# uJOVE5.net
KiCad netlist of a schematic drawn in EAGLE
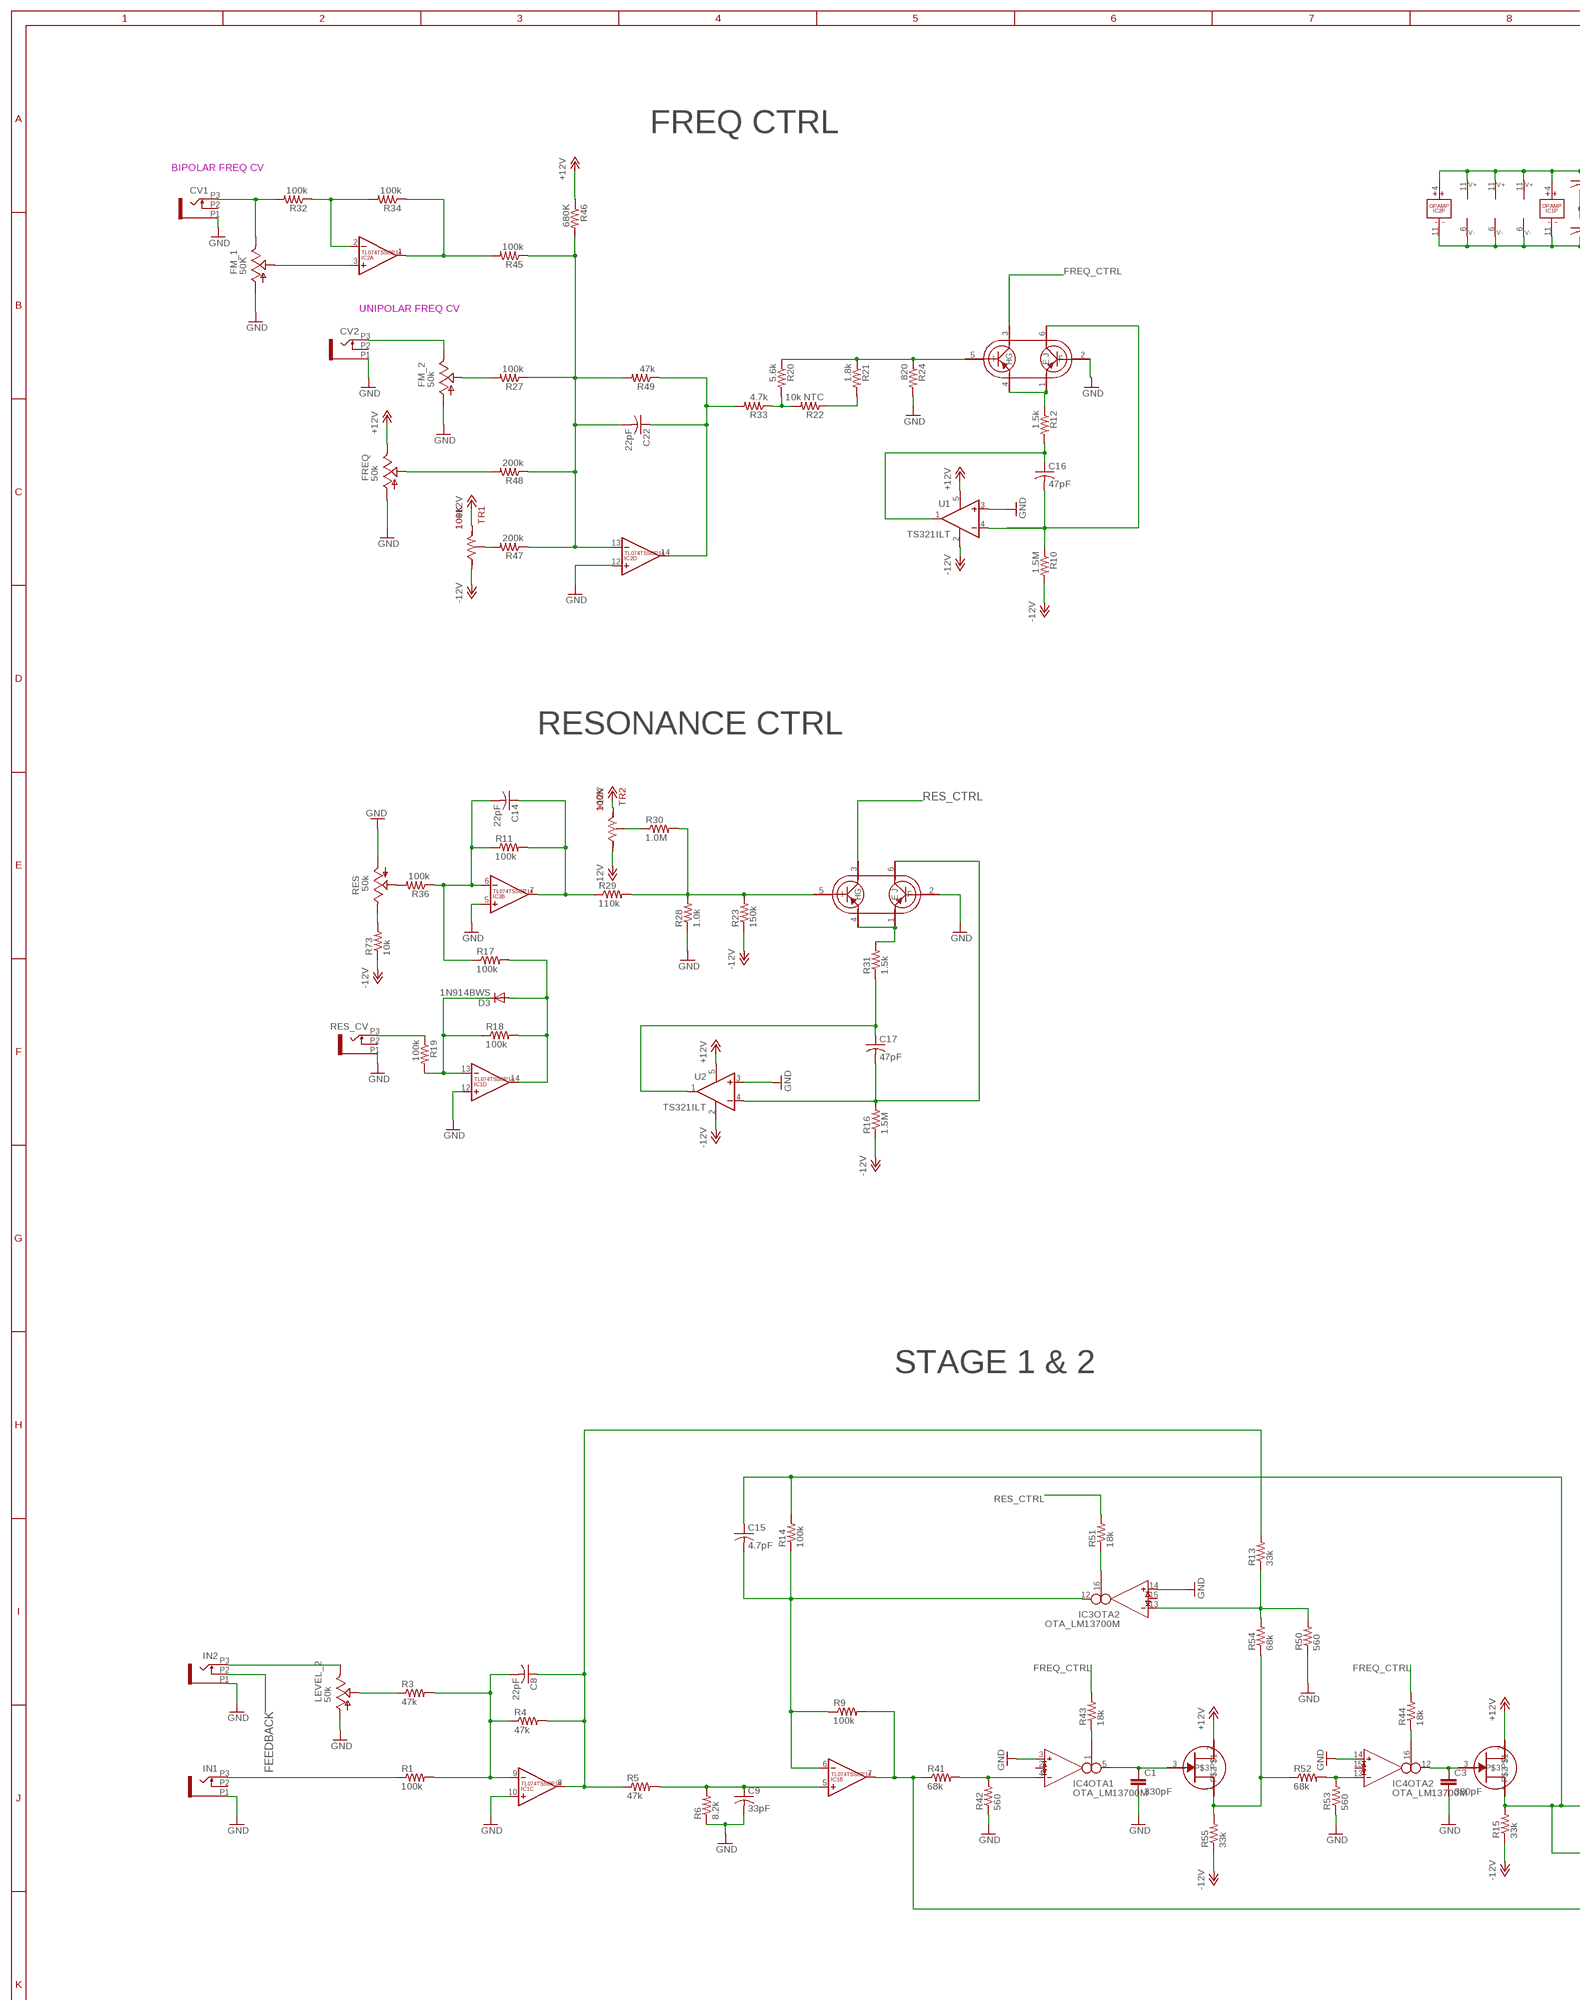
[diagram p0: schematic, sheet 1, part 1 of 3]
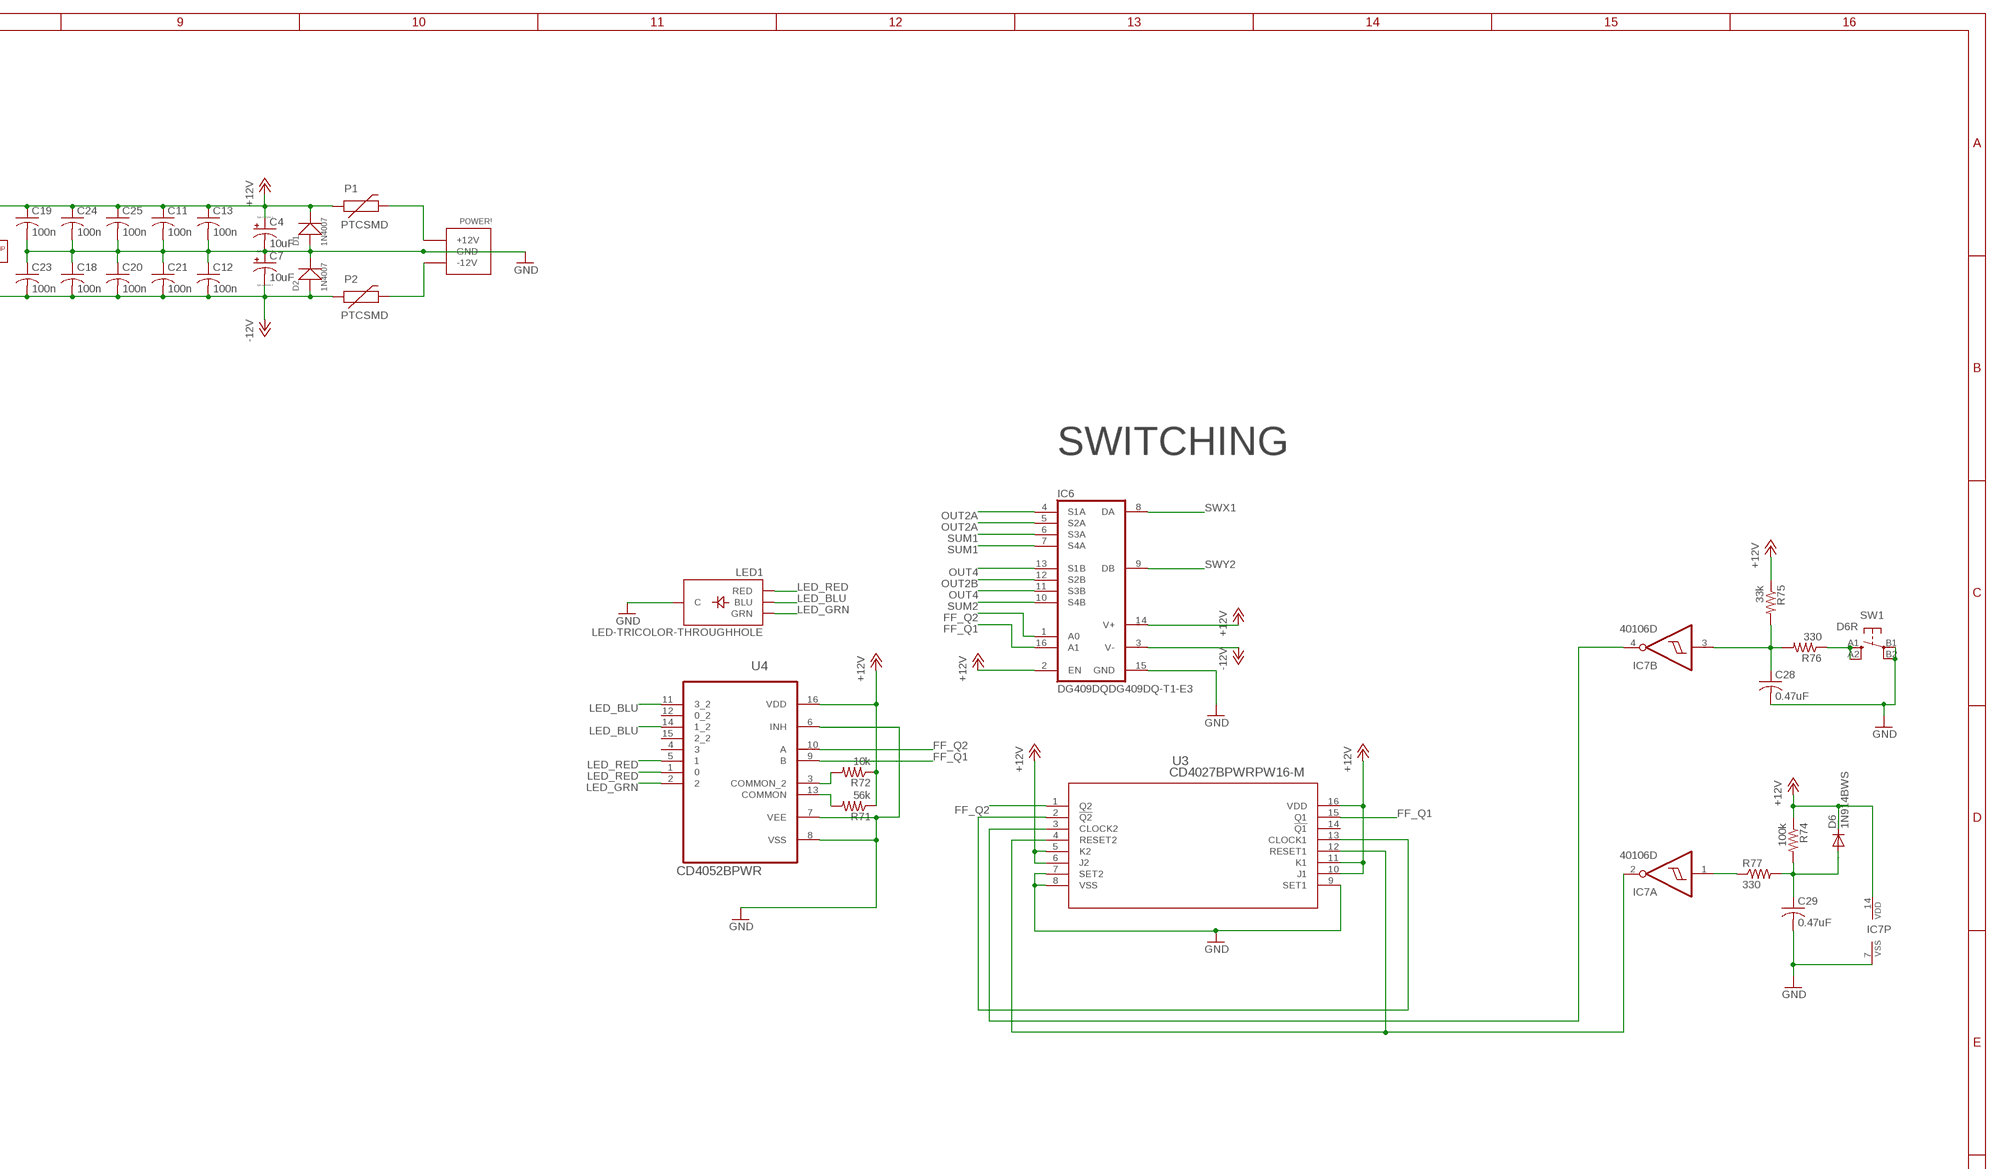
[diagram p1: schematic, sheet 1, part 2 of 3]
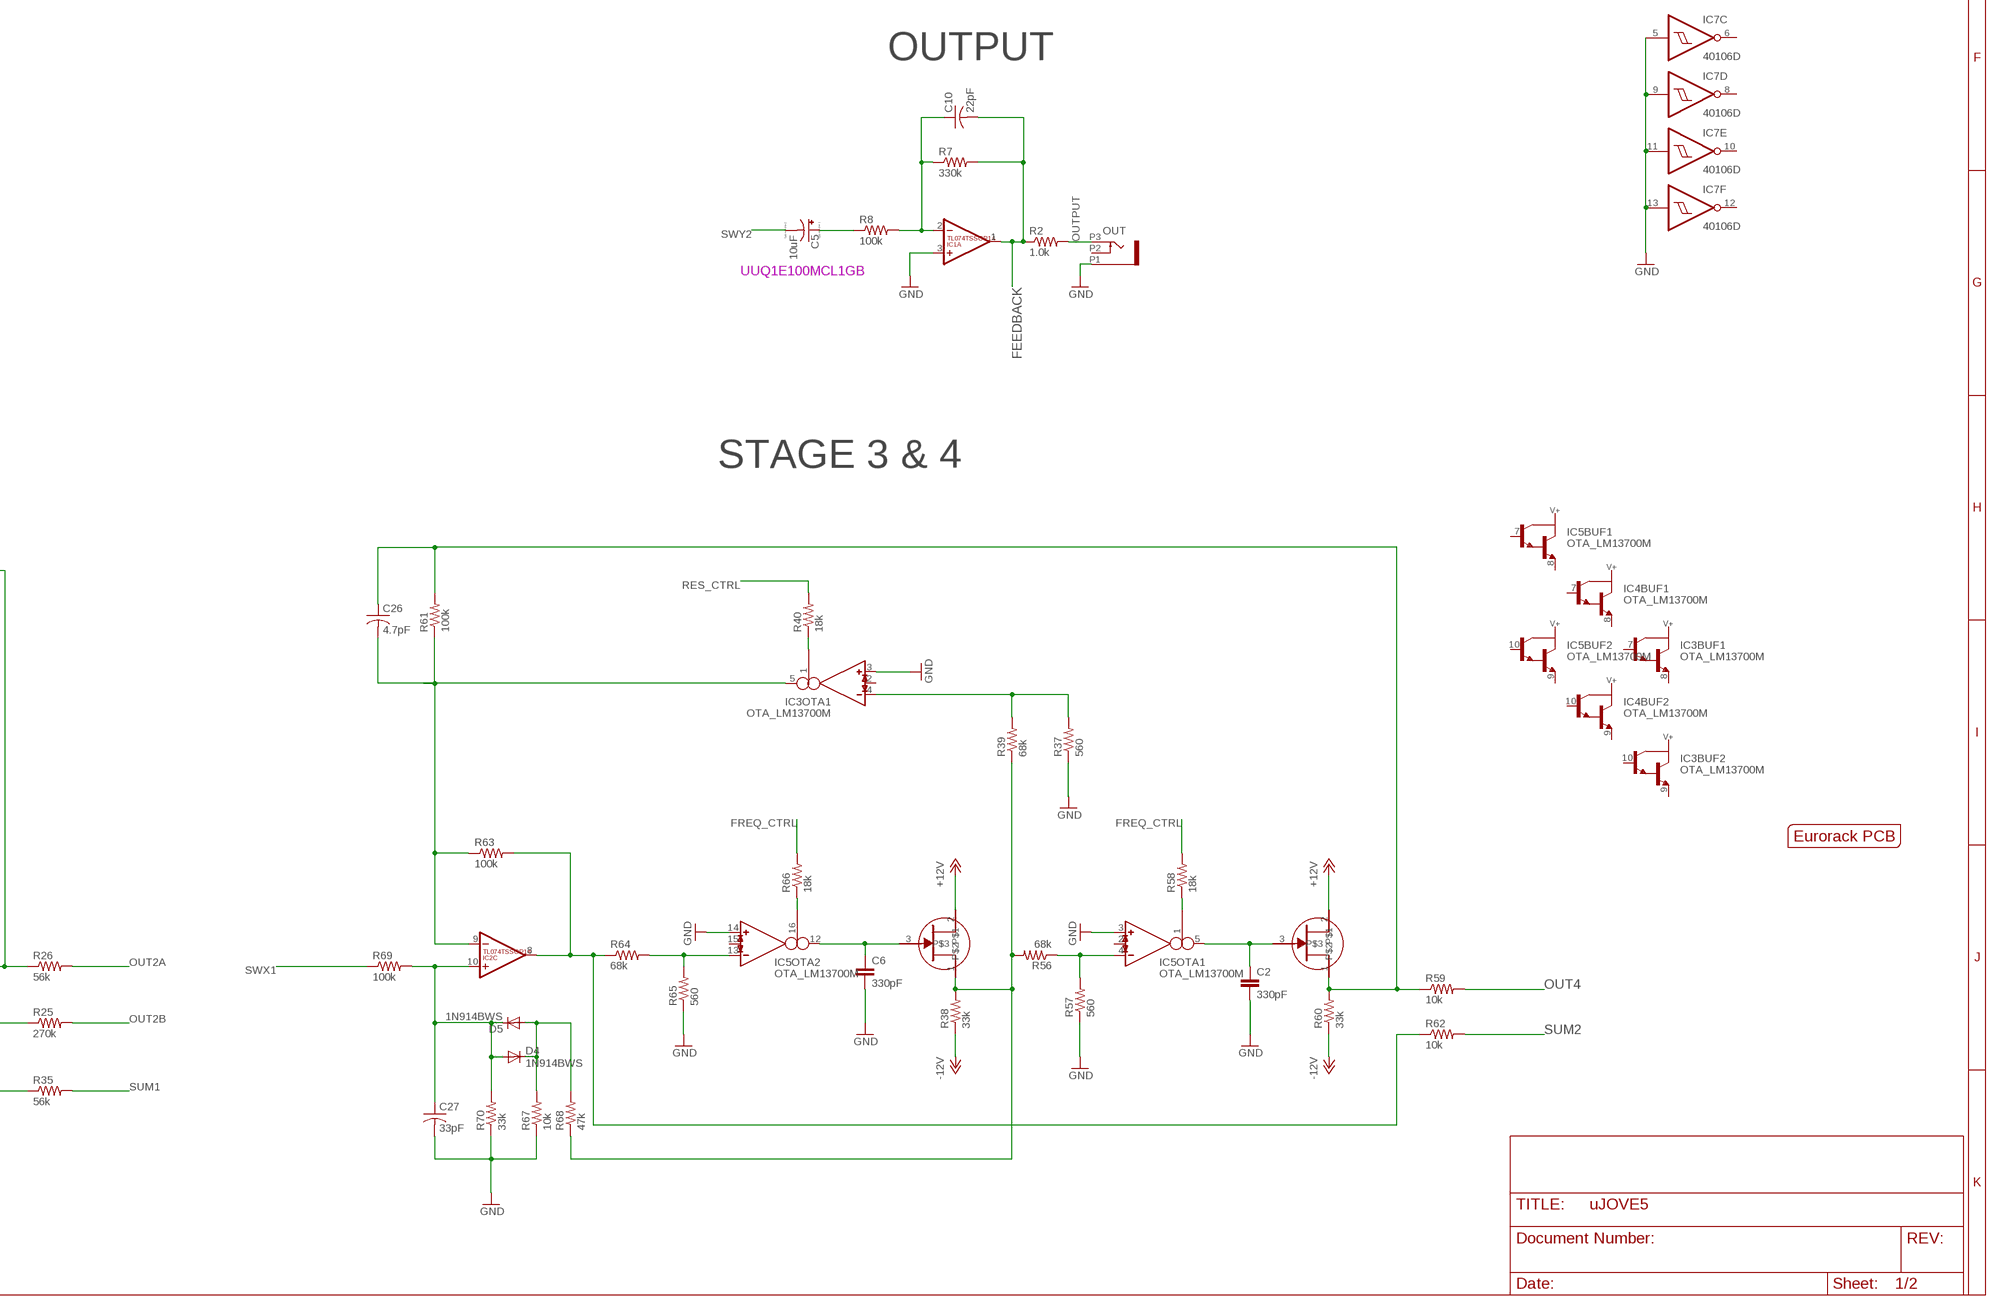
[diagram p2: schematic, sheet 1, part 3 of 3]

(export (version "E")
  (design (tool "Eeschema 10.0.6"))
  (components
    (comp (ref "C1")
      (value "330pF")
      (footprint "eagle-import:C5B5")
      (libsource (lib "eagle-import") (part "C5/5"))
    )
    (comp (ref "C2")
      (value "330pF")
      (footprint "eagle-import:C5B5")
      (libsource (lib "eagle-import") (part "C5/5"))
    )
    (comp (ref "C3")
      (value "330pF")
      (footprint "eagle-import:C5B5")
      (libsource (lib "eagle-import") (part "C5/5"))
    )
    (comp (ref "C4")
      (value "10uF")
      (footprint "eagle-import:PANASONIC_C")
      (libsource (lib "eagle-import") (part "CPOL-USC"))
    )
    (comp (ref "C5")
      (value "10uF")
      (footprint "eagle-import:PANASONIC_C")
      (libsource (lib "eagle-import") (part "CPOL-USC"))
    )
    (comp (ref "C6")
      (value "330pF")
      (footprint "eagle-import:C5B5")
      (libsource (lib "eagle-import") (part "C5/5"))
    )
    (comp (ref "C7")
      (value "10uF")
      (footprint "eagle-import:PANASONIC_C")
      (libsource (lib "eagle-import") (part "CPOL-USC"))
    )
    (comp (ref "C8")
      (value "22pF")
      (footprint "eagle-import:C0603")
      (libsource (lib "eagle-import") (part "C-USC0603"))
    )
    (comp (ref "C9")
      (value "33pF")
      (footprint "eagle-import:C0603")
      (libsource (lib "eagle-import") (part "C-USC0603"))
    )
    (comp (ref "C10")
      (value "22pF")
      (footprint "eagle-import:C0603")
      (libsource (lib "eagle-import") (part "C-USC0603"))
    )
    (comp (ref "C11")
      (value "100n")
      (footprint "eagle-import:C0603")
      (libsource (lib "eagle-import") (part "C-USC0603"))
    )
    (comp (ref "C12")
      (value "100n")
      (footprint "eagle-import:C0603")
      (libsource (lib "eagle-import") (part "C-USC0603"))
    )
    (comp (ref "C13")
      (value "100n")
      (footprint "eagle-import:C0603")
      (libsource (lib "eagle-import") (part "C-USC0603"))
    )
    (comp (ref "C14")
      (value "22pF")
      (footprint "eagle-import:C0603")
      (libsource (lib "eagle-import") (part "C-USC0603"))
    )
    (comp (ref "C15")
      (value "4.7pF")
      (footprint "eagle-import:C0603")
      (libsource (lib "eagle-import") (part "C-USC0603"))
    )
    (comp (ref "C16")
      (value "47pF")
      (footprint "eagle-import:C0603")
      (libsource (lib "eagle-import") (part "C-USC0603"))
    )
    (comp (ref "C17")
      (value "47pF")
      (footprint "eagle-import:C0603")
      (libsource (lib "eagle-import") (part "C-USC0603"))
    )
    (comp (ref "C18")
      (value "100n")
      (footprint "eagle-import:C0603")
      (libsource (lib "eagle-import") (part "C-USC0603"))
    )
    (comp (ref "C19")
      (value "100n")
      (footprint "eagle-import:C0603")
      (libsource (lib "eagle-import") (part "C-USC0603"))
    )
    (comp (ref "C20")
      (value "100n")
      (footprint "eagle-import:C0603")
      (libsource (lib "eagle-import") (part "C-USC0603"))
    )
    (comp (ref "C21")
      (value "100n")
      (footprint "eagle-import:C0603")
      (libsource (lib "eagle-import") (part "C-USC0603"))
    )
    (comp (ref "C22")
      (value "22pF")
      (footprint "eagle-import:C0603")
      (libsource (lib "eagle-import") (part "C-USC0603"))
    )
    (comp (ref "C23")
      (value "100n")
      (footprint "eagle-import:C0603")
      (libsource (lib "eagle-import") (part "C-USC0603"))
    )
    (comp (ref "C24")
      (value "100n")
      (footprint "eagle-import:C0603")
      (libsource (lib "eagle-import") (part "C-USC0603"))
    )
    (comp (ref "C25")
      (value "100n")
      (footprint "eagle-import:C0603")
      (libsource (lib "eagle-import") (part "C-USC0603"))
    )
    (comp (ref "C26")
      (value "4.7pF")
      (footprint "eagle-import:C0603")
      (libsource (lib "eagle-import") (part "C-USC0603"))
    )
    (comp (ref "C27")
      (value "33pF")
      (footprint "eagle-import:C0603")
      (libsource (lib "eagle-import") (part "C-USC0603"))
    )
    (comp (ref "C28")
      (value "0.47uF")
      (footprint "eagle-import:C0603")
      (libsource (lib "eagle-import") (part "C-USC0603"))
    )
    (comp (ref "C29")
      (value "0.47uF")
      (footprint "eagle-import:C0603")
      (libsource (lib "eagle-import") (part "C-USC0603"))
    )
    (comp (ref "CV1")
      (value "OG-PJ301_PJ301_THONKICONN")
      (footprint "eagle-import:OG-PJ301_WQP_PJ_301M6_NO_HOLE")
      (libsource (lib "eagle-import") (part "OG-PJ301_PJ301_THONKICONN"))
    )
    (comp (ref "CV2")
      (value "OG-PJ301_PJ301_THONKICONN")
      (footprint "eagle-import:OG-PJ301_WQP_PJ_301M6_NO_HOLE")
      (libsource (lib "eagle-import") (part "OG-PJ301_PJ301_THONKICONN"))
    )
    (comp (ref "D1")
      (value "1N4007")
      (footprint "eagle-import:DO-214AC")
      (libsource (lib "eagle-import") (part "DIODE-GEN-PURPOSE-1KV-1A(DO-214AC)"))
    )
    (comp (ref "D2")
      (value "1N4007")
      (footprint "eagle-import:DO-214AC")
      (libsource (lib "eagle-import") (part "DIODE-GEN-PURPOSE-1KV-1A(DO-214AC)"))
    )
    (comp (ref "D3")
      (value "1N914BWS")
      (footprint "eagle-import:SOD323-R")
      (libsource (lib "eagle-import") (part "DIODE-SOD323-R"))
    )
    (comp (ref "D4")
      (value "1N914BWS")
      (footprint "eagle-import:SOD323-R")
      (libsource (lib "eagle-import") (part "DIODE-SOD323-R"))
    )
    (comp (ref "D5")
      (value "1N914BWS")
      (footprint "eagle-import:SOD323-R")
      (libsource (lib "eagle-import") (part "DIODE-SOD323-R"))
    )
    (comp (ref "D6")
      (value "1N914BWS")
      (footprint "eagle-import:SOD323-R")
      (libsource (lib "eagle-import") (part "DIODE-SOD323-R"))
    )
    (comp (ref "FM_1")
      (value "50K")
      (footprint "eagle-import:OG-POTS_ALPS_POT_VERTICAL")
      (libsource (lib "eagle-import") (part "OG-POTS_POT_USVERTICAL"))
    )
    (comp (ref "FM_2")
      (value "50k")
      (footprint "eagle-import:OG-POTS_ALPS_POT_VERTICAL")
      (libsource (lib "eagle-import") (part "OG-POTS_POT_USVERTICAL"))
    )
    (comp (ref "FREQ")
      (value "50k")
      (footprint "eagle-import:OG-POTS_ALPS_POT_VERTICAL_PS")
      (libsource (lib "eagle-import") (part "OG-POTS_POT_USVERTICAL_PS"))
    )
    (comp (ref "IC1")
      (value "TL074TSSOP14")
      (footprint "eagle-import:TSSOP14")
      (libsource (lib "eagle-import") (part "TL074TSSOP14"))
    )
    (comp (ref "IC2")
      (value "TL074TSSOP14")
      (footprint "eagle-import:TSSOP14")
      (libsource (lib "eagle-import") (part "TL074TSSOP14"))
    )
    (comp (ref "IC3")
      (value "OTA_LM13700M")
      (footprint "eagle-import:OTA_SO16")
      (libsource (lib "eagle-import") (part "OTA_LM13700M"))
    )
    (comp (ref "IC4")
      (value "OTA_LM13700M")
      (footprint "eagle-import:OTA_SO16")
      (libsource (lib "eagle-import") (part "OTA_LM13700M"))
    )
    (comp (ref "IC5")
      (value "OTA_LM13700M")
      (footprint "eagle-import:OTA_SO16")
      (libsource (lib "eagle-import") (part "OTA_LM13700M"))
    )
    (comp (ref "IC6")
      (value "DG409DQDG409DQ-T1-E3")
      (footprint "eagle-import:TSSOP16")
      (libsource (lib "eagle-import") (part "DG409DQDG409DQ-T1-E3"))
    )
    (comp (ref "IC7")
      (value "40106D")
      (footprint "eagle-import:SO14")
      (libsource (lib "eagle-import") (part "40106D"))
    )
    (comp (ref "IN1")
      (value "OG-PJ301_PJ301_THONKICONN")
      (footprint "eagle-import:OG-PJ301_WQP_PJ_301M6_NO_HOLE")
      (libsource (lib "eagle-import") (part "OG-PJ301_PJ301_THONKICONN"))
    )
    (comp (ref "IN2")
      (value "OG-PJ301_PJ301_THONKICONN")
      (footprint "eagle-import:OG-PJ301_WQP_PJ_301M6_NO_HOLE")
      (libsource (lib "eagle-import") (part "OG-PJ301_PJ301_THONKICONN"))
    )
    (comp (ref "LED1")
      (value "LED-TRICOLOR-THROUGHHOLE")
      (footprint "eagle-import:LED-TRICOLOR-THROUGHHOLE")
      (libsource (lib "eagle-import") (part "LED-TRICOLOR-THROUGHHOLE"))
    )
    (comp (ref "LEVEL_2")
      (value "50k")
      (footprint "eagle-import:OG-POTS_ALPS_POT_VERTICAL")
      (libsource (lib "eagle-import") (part "OG-POTS_POT_USVERTICAL"))
    )
    (comp (ref "OUT")
      (value "OG-PJ301_PJ301_THONKICONN")
      (footprint "eagle-import:OG-PJ301_WQP_PJ_301M6_NO_HOLE")
      (libsource (lib "eagle-import") (part "OG-PJ301_PJ301_THONKICONN"))
    )
    (comp (ref "P1")
      (value "PTCSMD")
      (footprint "eagle-import:PTC-1206")
      (libsource (lib "eagle-import") (part "PTCSMD"))
    )
    (comp (ref "P2")
      (value "PTCSMD")
      (footprint "eagle-import:PTC-1206")
      (libsource (lib "eagle-import") (part "PTCSMD"))
    )
    (comp (ref "PCB1")
      (value "EURORACK_PCB")
      (footprint "eagle-import:EURORACK8HPPCB-S")
      (libsource (lib "eagle-import") (part "EURORACK_PCB"))
    )
    (comp (ref "POWER!")
      (value "POWER_SIMPLE")
      (footprint "eagle-import:2X05_SMT_HEADER")
      (libsource (lib "eagle-import") (part "POWER_SIMPLE"))
    )
    (comp (ref "Q1")
      (value "BCM857BS")
      (footprint "eagle-import:SOT65P210X110-6N")
      (libsource (lib "eagle-import") (part "BCM857BS"))
    )
    (comp (ref "Q2")
      (value "BCM857BS")
      (footprint "eagle-import:SOT65P210X110-6N")
      (libsource (lib "eagle-import") (part "BCM857BS"))
    )
    (comp (ref "Q3")
      (value "MMBFJ112MMBFJ112")
      (footprint "eagle-import:SOT23")
      (libsource (lib "eagle-import") (part "MMBFJ112MMBFJ112"))
    )
    (comp (ref "Q4")
      (value "MMBFJ112MMBFJ112")
      (footprint "eagle-import:SOT23")
      (libsource (lib "eagle-import") (part "MMBFJ112MMBFJ112"))
    )
    (comp (ref "Q5")
      (value "MMBFJ112MMBFJ112")
      (footprint "eagle-import:SOT23")
      (libsource (lib "eagle-import") (part "MMBFJ112MMBFJ112"))
    )
    (comp (ref "Q6")
      (value "MMBFJ112MMBFJ112")
      (footprint "eagle-import:SOT23")
      (libsource (lib "eagle-import") (part "MMBFJ112MMBFJ112"))
    )
    (comp (ref "R1")
      (value "100k")
      (footprint "eagle-import:R0603")
      (libsource (lib "eagle-import") (part "R-US_R0603"))
    )
    (comp (ref "R2")
      (value "1.0k")
      (footprint "eagle-import:R0603")
      (libsource (lib "eagle-import") (part "R-US_R0603"))
    )
    (comp (ref "R3")
      (value "47k")
      (footprint "eagle-import:R0603")
      (libsource (lib "eagle-import") (part "R-US_R0603"))
    )
    (comp (ref "R4")
      (value "47k")
      (footprint "eagle-import:R0603")
      (libsource (lib "eagle-import") (part "R-US_R0603"))
    )
    (comp (ref "R5")
      (value "47k")
      (footprint "eagle-import:R0603")
      (libsource (lib "eagle-import") (part "R-US_R0603"))
    )
    (comp (ref "R6")
      (value "8.2k")
      (footprint "eagle-import:R0603")
      (libsource (lib "eagle-import") (part "R-US_R0603"))
    )
    (comp (ref "R7")
      (value "330k")
      (footprint "eagle-import:R0603")
      (libsource (lib "eagle-import") (part "R-US_R0603"))
    )
    (comp (ref "R8")
      (value "100k")
      (footprint "eagle-import:R0603")
      (libsource (lib "eagle-import") (part "R-US_R0603"))
    )
    (comp (ref "R9")
      (value "100k")
      (footprint "eagle-import:R0603")
      (libsource (lib "eagle-import") (part "R-US_R0603"))
    )
    (comp (ref "R10")
      (value "1.5M")
      (footprint "eagle-import:R0603")
      (libsource (lib "eagle-import") (part "R-US_R0603"))
    )
    (comp (ref "R11")
      (value "100k")
      (footprint "eagle-import:R0603")
      (libsource (lib "eagle-import") (part "R-US_R0603"))
    )
    (comp (ref "R12")
      (value "1.5k")
      (footprint "eagle-import:R0603")
      (libsource (lib "eagle-import") (part "R-US_R0603"))
    )
    (comp (ref "R13")
      (value "33k")
      (footprint "eagle-import:R0603")
      (libsource (lib "eagle-import") (part "R-US_R0603"))
    )
    (comp (ref "R14")
      (value "100k")
      (footprint "eagle-import:R0603")
      (libsource (lib "eagle-import") (part "R-US_R0603"))
    )
    (comp (ref "R15")
      (value "33k")
      (footprint "eagle-import:R0603")
      (libsource (lib "eagle-import") (part "R-US_R0603"))
    )
    (comp (ref "R16")
      (value "1.5M")
      (footprint "eagle-import:R0603")
      (libsource (lib "eagle-import") (part "R-US_R0603"))
    )
    (comp (ref "R17")
      (value "100k")
      (footprint "eagle-import:R0603")
      (libsource (lib "eagle-import") (part "R-US_R0603"))
    )
    (comp (ref "R18")
      (value "100k")
      (footprint "eagle-import:R0603")
      (libsource (lib "eagle-import") (part "R-US_R0603"))
    )
    (comp (ref "R19")
      (value "100k")
      (footprint "eagle-import:R0603")
      (libsource (lib "eagle-import") (part "R-US_R0603"))
    )
    (comp (ref "R20")
      (value "5.6k")
      (footprint "eagle-import:R0603")
      (libsource (lib "eagle-import") (part "R-US_R0603"))
    )
    (comp (ref "R21")
      (value "1.8k")
      (footprint "eagle-import:R0603")
      (libsource (lib "eagle-import") (part "R-US_R0603"))
    )
    (comp (ref "R22")
      (value "10k NTC")
      (footprint "eagle-import:R0805")
      (libsource (lib "eagle-import") (part "resistor_348_R-US_R0805"))
    )
    (comp (ref "R23")
      (value "150k")
      (footprint "eagle-import:R0603")
      (libsource (lib "eagle-import") (part "R-US_R0603"))
    )
    (comp (ref "R24")
      (value "820")
      (footprint "eagle-import:R0603")
      (libsource (lib "eagle-import") (part "R-US_R0603"))
    )
    (comp (ref "R25")
      (value "270k")
      (footprint "eagle-import:R0603")
      (libsource (lib "eagle-import") (part "R-US_R0603"))
    )
    (comp (ref "R26")
      (value "56k")
      (footprint "eagle-import:R0603")
      (libsource (lib "eagle-import") (part "R-US_R0603"))
    )
    (comp (ref "R27")
      (value "100k")
      (footprint "eagle-import:R0603")
      (libsource (lib "eagle-import") (part "R-US_R0603"))
    )
    (comp (ref "R28")
      (value "1.0k")
      (footprint "eagle-import:R0603")
      (libsource (lib "eagle-import") (part "R-US_R0603"))
    )
    (comp (ref "R29")
      (value "110k")
      (footprint "eagle-import:R0603")
      (libsource (lib "eagle-import") (part "R-US_R0603"))
    )
    (comp (ref "R30")
      (value "1.0M")
      (footprint "eagle-import:R0603")
      (libsource (lib "eagle-import") (part "R-US_R0603"))
    )
    (comp (ref "R31")
      (value "1.5k")
      (footprint "eagle-import:R0603")
      (libsource (lib "eagle-import") (part "R-US_R0603"))
    )
    (comp (ref "R32")
      (value "100k")
      (footprint "eagle-import:R0603")
      (libsource (lib "eagle-import") (part "R-US_R0603"))
    )
    (comp (ref "R33")
      (value "4.7k")
      (footprint "eagle-import:R0603")
      (libsource (lib "eagle-import") (part "R-US_R0603"))
    )
    (comp (ref "R34")
      (value "100k")
      (footprint "eagle-import:R0603")
      (libsource (lib "eagle-import") (part "R-US_R0603"))
    )
    (comp (ref "R35")
      (value "56k")
      (footprint "eagle-import:R0603")
      (libsource (lib "eagle-import") (part "R-US_R0603"))
    )
    (comp (ref "R36")
      (value "100k")
      (footprint "eagle-import:R0603")
      (libsource (lib "eagle-import") (part "R-US_R0603"))
    )
    (comp (ref "R37")
      (value "560")
      (footprint "eagle-import:R0603")
      (libsource (lib "eagle-import") (part "R-US_R0603"))
    )
    (comp (ref "R38")
      (value "33k")
      (footprint "eagle-import:R0603")
      (libsource (lib "eagle-import") (part "R-US_R0603"))
    )
    (comp (ref "R39")
      (value "68k")
      (footprint "eagle-import:R0603")
      (libsource (lib "eagle-import") (part "R-US_R0603"))
    )
    (comp (ref "R40")
      (value "18k")
      (footprint "eagle-import:R0603")
      (libsource (lib "eagle-import") (part "R-US_R0603"))
    )
    (comp (ref "R41")
      (value "68k")
      (footprint "eagle-import:R0603")
      (libsource (lib "eagle-import") (part "R-US_R0603"))
    )
    (comp (ref "R42")
      (value "560")
      (footprint "eagle-import:R0603")
      (libsource (lib "eagle-import") (part "R-US_R0603"))
    )
    (comp (ref "R43")
      (value "18k")
      (footprint "eagle-import:R0603")
      (libsource (lib "eagle-import") (part "R-US_R0603"))
    )
    (comp (ref "R44")
      (value "18k")
      (footprint "eagle-import:R0603")
      (libsource (lib "eagle-import") (part "R-US_R0603"))
    )
    (comp (ref "R45")
      (value "100k")
      (footprint "eagle-import:R0603")
      (libsource (lib "eagle-import") (part "R-US_R0603"))
    )
    (comp (ref "R46")
      (value "680K")
      (footprint "eagle-import:R0603")
      (libsource (lib "eagle-import") (part "R-US_R0603"))
    )
    (comp (ref "R47")
      (value "200k")
      (footprint "eagle-import:R0603")
      (libsource (lib "eagle-import") (part "R-US_R0603"))
    )
    (comp (ref "R48")
      (value "200k")
      (footprint "eagle-import:R0603")
      (libsource (lib "eagle-import") (part "R-US_R0603"))
    )
    (comp (ref "R49")
      (value "47k")
      (footprint "eagle-import:R0603")
      (libsource (lib "eagle-import") (part "R-US_R0603"))
    )
    (comp (ref "R50")
      (value "560")
      (footprint "eagle-import:R0603")
      (libsource (lib "eagle-import") (part "R-US_R0603"))
    )
    (comp (ref "R51")
      (value "18k")
      (footprint "eagle-import:R0603")
      (libsource (lib "eagle-import") (part "R-US_R0603"))
    )
    (comp (ref "R52")
      (value "68k")
      (footprint "eagle-import:R0603")
      (libsource (lib "eagle-import") (part "R-US_R0603"))
    )
    (comp (ref "R53")
      (value "560")
      (footprint "eagle-import:R0603")
      (libsource (lib "eagle-import") (part "R-US_R0603"))
    )
    (comp (ref "R54")
      (value "68k")
      (footprint "eagle-import:R0603")
      (libsource (lib "eagle-import") (part "R-US_R0603"))
    )
    (comp (ref "R55")
      (value "33k")
      (footprint "eagle-import:R0603")
      (libsource (lib "eagle-import") (part "R-US_R0603"))
    )
    (comp (ref "R56")
      (value "68k")
      (footprint "eagle-import:R0603")
      (libsource (lib "eagle-import") (part "R-US_R0603"))
    )
    (comp (ref "R57")
      (value "560")
      (footprint "eagle-import:R0603")
      (libsource (lib "eagle-import") (part "R-US_R0603"))
    )
    (comp (ref "R58")
      (value "18k")
      (footprint "eagle-import:R0603")
      (libsource (lib "eagle-import") (part "R-US_R0603"))
    )
    (comp (ref "R59")
      (value "10k")
      (footprint "eagle-import:R0603")
      (libsource (lib "eagle-import") (part "R-US_R0603"))
    )
    (comp (ref "R60")
      (value "33k")
      (footprint "eagle-import:R0603")
      (libsource (lib "eagle-import") (part "R-US_R0603"))
    )
    (comp (ref "R61")
      (value "100k")
      (footprint "eagle-import:R0603")
      (libsource (lib "eagle-import") (part "R-US_R0603"))
    )
    (comp (ref "R62")
      (value "10k")
      (footprint "eagle-import:R0603")
      (libsource (lib "eagle-import") (part "R-US_R0603"))
    )
    (comp (ref "R63")
      (value "100k")
      (footprint "eagle-import:R0603")
      (libsource (lib "eagle-import") (part "R-US_R0603"))
    )
    (comp (ref "R64")
      (value "68k")
      (footprint "eagle-import:R0603")
      (libsource (lib "eagle-import") (part "R-US_R0603"))
    )
    (comp (ref "R65")
      (value "560")
      (footprint "eagle-import:R0603")
      (libsource (lib "eagle-import") (part "R-US_R0603"))
    )
    (comp (ref "R66")
      (value "18k")
      (footprint "eagle-import:R0603")
      (libsource (lib "eagle-import") (part "R-US_R0603"))
    )
    (comp (ref "R67")
      (value "10k")
      (footprint "eagle-import:R0603")
      (libsource (lib "eagle-import") (part "R-US_R0603"))
    )
    (comp (ref "R68")
      (value "47k")
      (footprint "eagle-import:R0603")
      (libsource (lib "eagle-import") (part "R-US_R0603"))
    )
    (comp (ref "R69")
      (value "100k")
      (footprint "eagle-import:R0603")
      (libsource (lib "eagle-import") (part "R-US_R0603"))
    )
    (comp (ref "R70")
      (value "33k")
      (footprint "eagle-import:R0603")
      (libsource (lib "eagle-import") (part "R-US_R0603"))
    )
    (comp (ref "R71")
      (value "56k")
      (footprint "eagle-import:R0603")
      (libsource (lib "eagle-import") (part "R-US_R0603"))
    )
    (comp (ref "R72")
      (value "10k")
      (footprint "eagle-import:R0603")
      (libsource (lib "eagle-import") (part "R-US_R0603"))
    )
    (comp (ref "R73")
      (value "10k")
      (footprint "eagle-import:R0603")
      (libsource (lib "eagle-import") (part "R-US_R0603"))
    )
    (comp (ref "R74")
      (value "100k")
      (footprint "eagle-import:R0603")
      (libsource (lib "eagle-import") (part "R-US_R0603"))
    )
    (comp (ref "R75")
      (value "33k")
      (footprint "eagle-import:R0603")
      (libsource (lib "eagle-import") (part "R-US_R0603"))
    )
    (comp (ref "R76")
      (value "330")
      (footprint "eagle-import:R0603")
      (libsource (lib "eagle-import") (part "R-US_R0603"))
    )
    (comp (ref "R77")
      (value "330")
      (footprint "eagle-import:R0603")
      (libsource (lib "eagle-import") (part "R-US_R0603"))
    )
    (comp (ref "RES")
      (value "50k")
      (footprint "eagle-import:OG-POTS_ALPS_POT_VERTICAL_PS")
      (libsource (lib "eagle-import") (part "OG-POTS_POT_USVERTICAL_PS"))
    )
    (comp (ref "RES_CV")
      (value "OG-PJ301_PJ301_THONKICONN")
      (footprint "eagle-import:OG-PJ301_WQP_PJ_301M6_NO_HOLE")
      (libsource (lib "eagle-import") (part "OG-PJ301_PJ301_THONKICONN"))
    )
    (comp (ref "SW1")
      (value "D6R")
      (footprint "eagle-import:D6R")
      (libsource (lib "eagle-import") (part "D6R"))
    )
    (comp (ref "TR1")
      (value "100K")
      (footprint "eagle-import:TC33X-2")
      (fields (field (name "ARROW_PART_NUMBER") "TC33X-2-104E") (field (name "RS_PART_NUMBER") "1673550"))
      (libsource (lib "eagle-import") (part "TC33X-2-104E"))
    )
    (comp (ref "TR2")
      (value "100K")
      (footprint "eagle-import:TC33X-2")
      (fields (field (name "ARROW_PART_NUMBER") "TC33X-2-104E") (field (name "RS_PART_NUMBER") "1673550"))
      (libsource (lib "eagle-import") (part "TC33X-2-104E"))
    )
    (comp (ref "U1")
      (value "TS321ILT")
      (footprint "eagle-import:SOT23-5")
      (fields (field (name "MF") "STMicroelectronics") (field (name "MP") "TS321I"))
      (libsource (lib "eagle-import") (part "TS321IDBV"))
    )
    (comp (ref "U2")
      (value "TS321ILT")
      (footprint "eagle-import:SOT23-5")
      (fields (field (name "MF") "STMicroelectronics") (field (name "MP") "TS321I"))
      (libsource (lib "eagle-import") (part "TS321IDBV"))
    )
    (comp (ref "U3")
      (value "CD4027BPWRPW16-M")
      (footprint "eagle-import:PW16-M")
      (fields (field (name "MANUFACTURER_PART_NUMBER") "CD4027BPWR"))
      (libsource (lib "eagle-import") (part "CD4027BPWRPW16-M"))
    )
    (comp (ref "U4")
      (value "CD4052BPWR")
      (footprint "eagle-import:SOP65P640X120-16N")
      (fields (field (name "MF") "Texas Instruments"))
      (libsource (lib "eagle-import") (part "CD4052BPWR"))
    )
  )
  (nets
    (net (code "1") (name "+12V") (class "Default")
      (node (ref "C11") (pin "1") (pinfunction "1_1") (pintype "passive"))
      (node (ref "C13") (pin "1") (pinfunction "1_1") (pintype "passive"))
      (node (ref "C19") (pin "1") (pinfunction "1_1") (pintype "passive"))
      (node (ref "C24") (pin "1") (pinfunction "1_1") (pintype "passive"))
      (node (ref "C25") (pin "1") (pinfunction "1_1") (pintype "passive"))
      (node (ref "C4") (pin "+") (pinfunction "+_+") (pintype "passive"))
      (node (ref "D1") (pin "2") (pinfunction "-_2") (pintype "passive"))
      (node (ref "D6") (pin "C") (pinfunction "C_C") (pintype "passive"))
      (node (ref "FREQ") (pin "P$1") (pinfunction "E_P$1") (pintype "passive"))
      (node (ref "IC1") (pin "4") (pinfunction "V+_4") (pintype "power_in"))
      (node (ref "IC2") (pin "4") (pinfunction "V+_4") (pintype "power_in"))
      (node (ref "IC3") (pin "11") (pinfunction "V+_11") (pintype "power_in"))
      (node (ref "IC4") (pin "11") (pinfunction "V+_11") (pintype "power_in"))
      (node (ref "IC5") (pin "11") (pinfunction "V+_11") (pintype "power_in"))
      (node (ref "IC6") (pin "14") (pinfunction "V+_14") (pintype "power_in"))
      (node (ref "IC6") (pin "2") (pinfunction "EN_2") (pintype "input"))
      (node (ref "IC7") (pin "14") (pinfunction "VDD_14") (pintype "power_in"))
      (node (ref "P1") (pin "1") (pinfunction "1_1") (pintype "bidirectional"))
      (node (ref "Q3") (pin "2") (pinfunction "P$2_2") (pintype "bidirectional"))
      (node (ref "Q4") (pin "2") (pinfunction "P$2_2") (pintype "bidirectional"))
      (node (ref "Q5") (pin "2") (pinfunction "P$2_2") (pintype "bidirectional"))
      (node (ref "Q6") (pin "2") (pinfunction "P$2_2") (pintype "bidirectional"))
      (node (ref "R46") (pin "1") (pinfunction "1_1") (pintype "passive"))
      (node (ref "R71") (pin "1") (pinfunction "1_1") (pintype "passive"))
      (node (ref "R72") (pin "1") (pinfunction "1_1") (pintype "passive"))
      (node (ref "R74") (pin "1") (pinfunction "1_1") (pintype "passive"))
      (node (ref "R75") (pin "1") (pinfunction "1_1") (pintype "passive"))
      (node (ref "TR1") (pin "1") (pinfunction "P$1_1") (pintype "bidirectional"))
      (node (ref "TR2") (pin "1") (pinfunction "P$1_1") (pintype "bidirectional"))
      (node (ref "U1") (pin "5") (pinfunction "V+_5") (pintype "power_in"))
      (node (ref "U2") (pin "5") (pinfunction "V+_5") (pintype "power_in"))
      (node (ref "U3") (pin "10") (pinfunction "J1_10") (pintype "input"))
      (node (ref "U3") (pin "11") (pinfunction "K1_11") (pintype "input"))
      (node (ref "U3") (pin "16") (pinfunction "VDD_16") (pintype "power_in"))
      (node (ref "U3") (pin "5") (pinfunction "K2_5") (pintype "input"))
      (node (ref "U3") (pin "6") (pinfunction "J2_6") (pintype "input"))
      (node (ref "U4") (pin "16") (pinfunction "VDD_16") (pintype "power_in"))
    )
    (net (code "2") (name "-12V") (class "Default")
      (node (ref "C12") (pin "2") (pinfunction "2_2") (pintype "passive"))
      (node (ref "C18") (pin "2") (pinfunction "2_2") (pintype "passive"))
      (node (ref "C20") (pin "2") (pinfunction "2_2") (pintype "passive"))
      (node (ref "C21") (pin "2") (pinfunction "2_2") (pintype "passive"))
      (node (ref "C23") (pin "2") (pinfunction "2_2") (pintype "passive"))
      (node (ref "C7") (pin "-") (pinfunction "-_-") (pintype "passive"))
      (node (ref "D2") (pin "1") (pinfunction "+_1") (pintype "passive"))
      (node (ref "IC1") (pin "11") (pinfunction "V-_11") (pintype "power_in"))
      (node (ref "IC2") (pin "11") (pinfunction "V-_11") (pintype "power_in"))
      (node (ref "IC3") (pin "6") (pinfunction "V-_6") (pintype "power_in"))
      (node (ref "IC4") (pin "6") (pinfunction "V-_6") (pintype "power_in"))
      (node (ref "IC5") (pin "6") (pinfunction "V-_6") (pintype "power_in"))
      (node (ref "IC6") (pin "3") (pinfunction "V-_3") (pintype "power_in"))
      (node (ref "P2") (pin "1") (pinfunction "1_1") (pintype "bidirectional"))
      (node (ref "R10") (pin "2") (pinfunction "2_2") (pintype "passive"))
      (node (ref "R15") (pin "1") (pinfunction "1_1") (pintype "passive"))
      (node (ref "R16") (pin "1") (pinfunction "1_1") (pintype "passive"))
      (node (ref "R23") (pin "1") (pinfunction "1_1") (pintype "passive"))
      (node (ref "R38") (pin "1") (pinfunction "1_1") (pintype "passive"))
      (node (ref "R55") (pin "1") (pinfunction "1_1") (pintype "passive"))
      (node (ref "R60") (pin "1") (pinfunction "1_1") (pintype "passive"))
      (node (ref "R73") (pin "1") (pinfunction "1_1") (pintype "passive"))
      (node (ref "TR1") (pin "3") (pinfunction "P$3_3") (pintype "bidirectional"))
      (node (ref "TR2") (pin "3") (pinfunction "P$3_3") (pintype "bidirectional"))
      (node (ref "U1") (pin "2") (pinfunction "V-_2") (pintype "power_in"))
      (node (ref "U2") (pin "2") (pinfunction "V-_2") (pintype "power_in"))
    )
    (net (code "3") (name "FEEDBACK") (class "Default")
      (node (ref "C10") (pin "2") (pinfunction "2_2") (pintype "passive"))
      (node (ref "IC1") (pin "1") (pinfunction "OUT_1") (pintype "output"))
      (node (ref "IN2") (pin "P2") (pinfunction "2_P2") (pintype "passive"))
      (node (ref "R2") (pin "1") (pinfunction "1_1") (pintype "passive"))
      (node (ref "R7") (pin "2") (pinfunction "2_2") (pintype "passive"))
    )
    (net (code "4") (name "FF_Q1") (class "Default")
      (node (ref "IC6") (pin "16") (pinfunction "A1_16") (pintype "input"))
      (node (ref "U3") (pin "15") (pinfunction "Q1_15") (pintype "output"))
      (node (ref "U4") (pin "9") (pinfunction "B_9") (pintype "input"))
    )
    (net (code "5") (name "FF_Q2") (class "Default")
      (node (ref "IC6") (pin "1") (pinfunction "A0_1") (pintype "input"))
      (node (ref "U3") (pin "1") (pinfunction "Q2_1") (pintype "output"))
      (node (ref "U4") (pin "10") (pinfunction "A_10") (pintype "input"))
    )
    (net (code "6") (name "FREQ_CTRL") (class "Default")
      (node (ref "Q1") (pin "3") (pinfunction "G_3") (pintype "bidirectional"))
      (node (ref "R43") (pin "2") (pinfunction "2_2") (pintype "passive"))
      (node (ref "R44") (pin "2") (pinfunction "2_2") (pintype "passive"))
      (node (ref "R58") (pin "2") (pinfunction "2_2") (pintype "passive"))
      (node (ref "R66") (pin "2") (pinfunction "2_2") (pintype "passive"))
    )
    (net (code "7") (name "GND") (class "Default")
      (node (ref "C1") (pin "2") (pinfunction "2_2") (pintype "passive"))
      (node (ref "C11") (pin "2") (pinfunction "2_2") (pintype "passive"))
      (node (ref "C12") (pin "1") (pinfunction "1_1") (pintype "passive"))
      (node (ref "C13") (pin "2") (pinfunction "2_2") (pintype "passive"))
      (node (ref "C18") (pin "1") (pinfunction "1_1") (pintype "passive"))
      (node (ref "C19") (pin "2") (pinfunction "2_2") (pintype "passive"))
      (node (ref "C2") (pin "2") (pinfunction "2_2") (pintype "passive"))
      (node (ref "C20") (pin "1") (pinfunction "1_1") (pintype "passive"))
      (node (ref "C21") (pin "1") (pinfunction "1_1") (pintype "passive"))
      (node (ref "C23") (pin "1") (pinfunction "1_1") (pintype "passive"))
      (node (ref "C24") (pin "2") (pinfunction "2_2") (pintype "passive"))
      (node (ref "C25") (pin "2") (pinfunction "2_2") (pintype "passive"))
      (node (ref "C27") (pin "2") (pinfunction "2_2") (pintype "passive"))
      (node (ref "C28") (pin "2") (pinfunction "2_2") (pintype "passive"))
      (node (ref "C29") (pin "2") (pinfunction "2_2") (pintype "passive"))
      (node (ref "C3") (pin "2") (pinfunction "2_2") (pintype "passive"))
      (node (ref "C4") (pin "-") (pinfunction "-_-") (pintype "passive"))
      (node (ref "C6") (pin "2") (pinfunction "2_2") (pintype "passive"))
      (node (ref "C7") (pin "+") (pinfunction "+_+") (pintype "passive"))
      (node (ref "C9") (pin "2") (pinfunction "2_2") (pintype "passive"))
      (node (ref "CV1") (pin "P1") (pinfunction "1_P1") (pintype "passive"))
      (node (ref "CV2") (pin "P1") (pinfunction "1_P1") (pintype "passive"))
      (node (ref "D1") (pin "1") (pinfunction "+_1") (pintype "passive"))
      (node (ref "D2") (pin "2") (pinfunction "-_2") (pintype "passive"))
      (node (ref "FM_1") (pin "P$3") (pinfunction "A_P$3") (pintype "passive"))
      (node (ref "FM_2") (pin "P$3") (pinfunction "A_P$3") (pintype "passive"))
      (node (ref "FREQ") (pin "P$3") (pinfunction "A_P$3") (pintype "passive"))
      (node (ref "IC1") (pin "10") (pinfunction "+IN_10") (pintype "input"))
      (node (ref "IC1") (pin "12") (pinfunction "+IN_12") (pintype "input"))
      (node (ref "IC1") (pin "3") (pinfunction "+IN_3") (pintype "input"))
      (node (ref "IC2") (pin "12") (pinfunction "+IN_12") (pintype "input"))
      (node (ref "IC2") (pin "5") (pinfunction "+IN_5") (pintype "input"))
      (node (ref "IC3") (pin "14") (pinfunction "IN_P_14") (pintype "input"))
      (node (ref "IC3") (pin "3") (pinfunction "IN_P_3") (pintype "input"))
      (node (ref "IC4") (pin "14") (pinfunction "IN_P_14") (pintype "input"))
      (node (ref "IC4") (pin "3") (pinfunction "IN_P_3") (pintype "input"))
      (node (ref "IC5") (pin "14") (pinfunction "IN_P_14") (pintype "input"))
      (node (ref "IC5") (pin "3") (pinfunction "IN_P_3") (pintype "input"))
      (node (ref "IC6") (pin "15") (pinfunction "GND_15") (pintype "power_in"))
      (node (ref "IC7") (pin "11") (pinfunction "I_11") (pintype "input"))
      (node (ref "IC7") (pin "13") (pinfunction "I_13") (pintype "input"))
      (node (ref "IC7") (pin "5") (pinfunction "I_5") (pintype "input"))
      (node (ref "IC7") (pin "7") (pinfunction "VSS_7") (pintype "power_in"))
      (node (ref "IC7") (pin "9") (pinfunction "I_9") (pintype "input"))
      (node (ref "IN1") (pin "P1") (pinfunction "1_P1") (pintype "passive"))
      (node (ref "IN2") (pin "P1") (pinfunction "1_P1") (pintype "passive"))
      (node (ref "LED1") (pin "GND") (pinfunction "C_GND") (pintype "bidirectional"))
      (node (ref "LEVEL_2") (pin "P$3") (pinfunction "A_P$3") (pintype "passive"))
      (node (ref "OUT") (pin "P1") (pinfunction "1_P1") (pintype "passive"))
      (node (ref "POWER!") (pin "3") (pinfunction "GND_3") (pintype "bidirectional"))
      (node (ref "POWER!") (pin "4") (pinfunction "GND_4") (pintype "bidirectional"))
      (node (ref "POWER!") (pin "5") (pinfunction "GND_5") (pintype "bidirectional"))
      (node (ref "POWER!") (pin "6") (pinfunction "GND_6") (pintype "bidirectional"))
      (node (ref "POWER!") (pin "7") (pinfunction "GND_7") (pintype "bidirectional"))
      (node (ref "POWER!") (pin "8") (pinfunction "GND_8") (pintype "bidirectional"))
      (node (ref "Q1") (pin "2") (pinfunction "F_2") (pintype "bidirectional"))
      (node (ref "Q2") (pin "2") (pinfunction "F_2") (pintype "bidirectional"))
      (node (ref "R24") (pin "2") (pinfunction "2_2") (pintype "passive"))
      (node (ref "R28") (pin "1") (pinfunction "1_1") (pintype "passive"))
      (node (ref "R37") (pin "1") (pinfunction "1_1") (pintype "passive"))
      (node (ref "R42") (pin "1") (pinfunction "1_1") (pintype "passive"))
      (node (ref "R50") (pin "1") (pinfunction "1_1") (pintype "passive"))
      (node (ref "R53") (pin "1") (pinfunction "1_1") (pintype "passive"))
      (node (ref "R57") (pin "1") (pinfunction "1_1") (pintype "passive"))
      (node (ref "R6") (pin "1") (pinfunction "1_1") (pintype "passive"))
      (node (ref "R65") (pin "1") (pinfunction "1_1") (pintype "passive"))
      (node (ref "R67") (pin "1") (pinfunction "1_1") (pintype "passive"))
      (node (ref "R70") (pin "1") (pinfunction "1_1") (pintype "passive"))
      (node (ref "RES") (pin "P$3") (pinfunction "A_P$3") (pintype "passive"))
      (node (ref "RES_CV") (pin "P1") (pinfunction "1_P1") (pintype "passive"))
      (node (ref "SW1") (pin "B1") (pinfunction "P_B1") (pintype "passive"))
      (node (ref "SW1") (pin "B2") (pinfunction "P1_B2") (pintype "passive"))
      (node (ref "U1") (pin "3") (pinfunction "+IN_3") (pintype "input"))
      (node (ref "U2") (pin "3") (pinfunction "+IN_3") (pintype "input"))
      (node (ref "U3") (pin "7") (pinfunction "SET2_7") (pintype "passive"))
      (node (ref "U3") (pin "8") (pinfunction "VSS_8") (pintype "power_in"))
      (node (ref "U3") (pin "9") (pinfunction "SET1_9") (pintype "passive"))
      (node (ref "U4") (pin "6") (pinfunction "INH_6") (pintype "input"))
      (node (ref "U4") (pin "7") (pinfunction "VEE_7") (pintype "power_in"))
      (node (ref "U4") (pin "8") (pinfunction "VSS_8") (pintype "power_in"))
    )
    (net (code "8") (name "LED_BLU") (class "Default")
      (node (ref "LED1") (pin "BLU") (pinfunction "BLU_BLU") (pintype "bidirectional"))
      (node (ref "U4") (pin "11") (pinfunction "3_2_11") (pintype "bidirectional"))
      (node (ref "U4") (pin "14") (pinfunction "1_2_14") (pintype "bidirectional"))
    )
    (net (code "9") (name "LED_GRN") (class "Default")
      (node (ref "LED1") (pin "GRN") (pinfunction "GRN_GRN") (pintype "bidirectional"))
      (node (ref "U4") (pin "2") (pinfunction "2_2") (pintype "input"))
    )
    (net (code "10") (name "LED_RED") (class "Default")
      (node (ref "LED1") (pin "RED") (pinfunction "RED_RED") (pintype "bidirectional"))
      (node (ref "U4") (pin "1") (pinfunction "0_1") (pintype "input"))
      (node (ref "U4") (pin "5") (pinfunction "1_5") (pintype "bidirectional"))
    )
    (net (code "11") (name "Net-(C5-Pad+)") (class "Default")
      (node (ref "C5") (pin "+") (pinfunction "+_+") (pintype "passive"))
      (node (ref "R8") (pin "1") (pinfunction "1_1") (pintype "passive"))
    )
    (net (code "12") (name "Net-(C29-Pad1)") (class "Default")
      (node (ref "C29") (pin "1") (pinfunction "1_1") (pintype "passive"))
      (node (ref "D6") (pin "A") (pinfunction "A_A") (pintype "passive"))
      (node (ref "R74") (pin "2") (pinfunction "2_2") (pintype "passive"))
      (node (ref "R77") (pin "2") (pinfunction "2_2") (pintype "passive"))
    )
    (net (code "13") (name "Net-(CV1-3)") (class "Default")
      (node (ref "CV1") (pin "P3") (pinfunction "3_P3") (pintype "passive"))
      (node (ref "FM_1") (pin "P$1") (pinfunction "E_P$1") (pintype "passive"))
      (node (ref "R32") (pin "2") (pinfunction "2_2") (pintype "passive"))
    )
    (net (code "14") (name "Net-(CV2-3)") (class "Default")
      (node (ref "CV2") (pin "P3") (pinfunction "3_P3") (pintype "passive"))
      (node (ref "FM_2") (pin "P$1") (pinfunction "E_P$1") (pintype "passive"))
    )
    (net (code "15") (name "Net-(D4-PadC)") (class "Default")
      (node (ref "D4") (pin "C") (pinfunction "C_C") (pintype "passive"))
      (node (ref "D5") (pin "A") (pinfunction "A_A") (pintype "passive"))
      (node (ref "R67") (pin "2") (pinfunction "2_2") (pintype "passive"))
      (node (ref "R68") (pin "2") (pinfunction "2_2") (pintype "passive"))
    )
    (net (code "16") (name "Net-(FM_1-S)") (class "Default")
      (node (ref "FM_1") (pin "P$2") (pinfunction "S_P$2") (pintype "passive"))
      (node (ref "IC2") (pin "3") (pinfunction "+IN_3") (pintype "input"))
    )
    (net (code "17") (name "Net-(FM_2-S)") (class "Default")
      (node (ref "FM_2") (pin "P$2") (pinfunction "S_P$2") (pintype "passive"))
      (node (ref "R27") (pin "2") (pinfunction "2_2") (pintype "passive"))
    )
    (net (code "18") (name "Net-(FREQ-S)") (class "Default")
      (node (ref "FREQ") (pin "P$2") (pinfunction "S_P$2") (pintype "passive"))
      (node (ref "R48") (pin "2") (pinfunction "2_2") (pintype "passive"))
    )
    (net (code "19") (name "Net-(IC1A--IN)") (class "Default")
      (node (ref "C10") (pin "1") (pinfunction "1_1") (pintype "passive"))
      (node (ref "IC1") (pin "2") (pinfunction "-IN_2") (pintype "input"))
      (node (ref "R7") (pin "1") (pinfunction "1_1") (pintype "passive"))
      (node (ref "R8") (pin "2") (pinfunction "2_2") (pintype "passive"))
    )
    (net (code "20") (name "Net-(IC1B-+IN)") (class "Default")
      (node (ref "C9") (pin "1") (pinfunction "1_1") (pintype "passive"))
      (node (ref "IC1") (pin "5") (pinfunction "+IN_5") (pintype "input"))
      (node (ref "R5") (pin "2") (pinfunction "2_2") (pintype "passive"))
      (node (ref "R6") (pin "2") (pinfunction "2_2") (pintype "passive"))
    )
    (net (code "21") (name "Net-(IC1B--IN)") (class "Default")
      (node (ref "C15") (pin "2") (pinfunction "2_2") (pintype "passive"))
      (node (ref "IC1") (pin "6") (pinfunction "-IN_6") (pintype "input"))
      (node (ref "IC3") (pin "12") (pinfunction "OUT_12") (pintype "output"))
      (node (ref "R14") (pin "1") (pinfunction "1_1") (pintype "passive"))
      (node (ref "R9") (pin "1") (pinfunction "1_1") (pintype "passive"))
    )
    (net (code "22") (name "Net-(IC1B-OUT)") (class "Default")
      (node (ref "IC1") (pin "7") (pinfunction "OUT_7") (pintype "output"))
      (node (ref "R35") (pin "1") (pinfunction "1_1") (pintype "passive"))
      (node (ref "R41") (pin "1") (pinfunction "1_1") (pintype "passive"))
      (node (ref "R9") (pin "2") (pinfunction "2_2") (pintype "passive"))
    )
    (net (code "23") (name "Net-(IC1C--IN)") (class "Default")
      (node (ref "C8") (pin "2") (pinfunction "2_2") (pintype "passive"))
      (node (ref "IC1") (pin "9") (pinfunction "-IN_9") (pintype "input"))
      (node (ref "R1") (pin "2") (pinfunction "2_2") (pintype "passive"))
      (node (ref "R3") (pin "2") (pinfunction "2_2") (pintype "passive"))
      (node (ref "R4") (pin "1") (pinfunction "1_1") (pintype "passive"))
    )
    (net (code "24") (name "Net-(IC1C-OUT)") (class "Default")
      (node (ref "C8") (pin "1") (pinfunction "1_1") (pintype "passive"))
      (node (ref "IC1") (pin "8") (pinfunction "OUT_8") (pintype "output"))
      (node (ref "R13") (pin "2") (pinfunction "2_2") (pintype "passive"))
      (node (ref "R4") (pin "2") (pinfunction "2_2") (pintype "passive"))
      (node (ref "R5") (pin "1") (pinfunction "1_1") (pintype "passive"))
    )
    (net (code "25") (name "Net-(IC1D--IN)") (class "Default")
      (node (ref "D3") (pin "C") (pinfunction "C_C") (pintype "passive"))
      (node (ref "IC1") (pin "13") (pinfunction "-IN_13") (pintype "input"))
      (node (ref "R18") (pin "1") (pinfunction "1_1") (pintype "passive"))
      (node (ref "R19") (pin "2") (pinfunction "2_2") (pintype "passive"))
    )
    (net (code "26") (name "Net-(IC1D-OUT)") (class "Default")
      (node (ref "D3") (pin "A") (pinfunction "A_A") (pintype "passive"))
      (node (ref "IC1") (pin "14") (pinfunction "OUT_14") (pintype "output"))
      (node (ref "R17") (pin "2") (pinfunction "2_2") (pintype "passive"))
      (node (ref "R18") (pin "2") (pinfunction "2_2") (pintype "passive"))
    )
    (net (code "27") (name "Net-(IC2A--IN)") (class "Default")
      (node (ref "IC2") (pin "2") (pinfunction "-IN_2") (pintype "input"))
      (node (ref "R32") (pin "1") (pinfunction "1_1") (pintype "passive"))
      (node (ref "R34") (pin "2") (pinfunction "2_2") (pintype "passive"))
    )
    (net (code "28") (name "Net-(IC2A-OUT)") (class "Default")
      (node (ref "IC2") (pin "1") (pinfunction "OUT_1") (pintype "output"))
      (node (ref "R34") (pin "1") (pinfunction "1_1") (pintype "passive"))
      (node (ref "R45") (pin "2") (pinfunction "2_2") (pintype "passive"))
    )
    (net (code "29") (name "Net-(IC2B--IN)") (class "Default")
      (node (ref "C14") (pin "2") (pinfunction "2_2") (pintype "passive"))
      (node (ref "IC2") (pin "6") (pinfunction "-IN_6") (pintype "input"))
      (node (ref "R11") (pin "1") (pinfunction "1_1") (pintype "passive"))
      (node (ref "R17") (pin "1") (pinfunction "1_1") (pintype "passive"))
      (node (ref "R36") (pin "1") (pinfunction "1_1") (pintype "passive"))
    )
    (net (code "30") (name "Net-(IC2B-OUT)") (class "Default")
      (node (ref "C14") (pin "1") (pinfunction "1_1") (pintype "passive"))
      (node (ref "IC2") (pin "7") (pinfunction "OUT_7") (pintype "output"))
      (node (ref "R11") (pin "2") (pinfunction "2_2") (pintype "passive"))
      (node (ref "R29") (pin "1") (pinfunction "1_1") (pintype "passive"))
    )
    (net (code "31") (name "Net-(IC2C-+IN)") (class "Default")
      (node (ref "C27") (pin "1") (pinfunction "1_1") (pintype "passive"))
      (node (ref "D4") (pin "A") (pinfunction "A_A") (pintype "passive"))
      (node (ref "D5") (pin "C") (pinfunction "C_C") (pintype "passive"))
      (node (ref "IC2") (pin "10") (pinfunction "+IN_10") (pintype "input"))
      (node (ref "R69") (pin "2") (pinfunction "2_2") (pintype "passive"))
      (node (ref "R70") (pin "2") (pinfunction "2_2") (pintype "passive"))
    )
    (net (code "32") (name "Net-(IC2C--IN)") (class "Default")
      (node (ref "C26") (pin "2") (pinfunction "2_2") (pintype "passive"))
      (node (ref "IC2") (pin "9") (pinfunction "-IN_9") (pintype "input"))
      (node (ref "IC3") (pin "5") (pinfunction "OUT_5") (pintype "output"))
      (node (ref "R61") (pin "1") (pinfunction "1_1") (pintype "passive"))
      (node (ref "R63") (pin "1") (pinfunction "1_1") (pintype "passive"))
    )
    (net (code "33") (name "Net-(IC2C-OUT)") (class "Default")
      (node (ref "IC2") (pin "8") (pinfunction "OUT_8") (pintype "output"))
      (node (ref "R62") (pin "1") (pinfunction "1_1") (pintype "passive"))
      (node (ref "R63") (pin "2") (pinfunction "2_2") (pintype "passive"))
      (node (ref "R64") (pin "1") (pinfunction "1_1") (pintype "passive"))
    )
    (net (code "34") (name "Net-(IC2D--IN)") (class "Default")
      (node (ref "C22") (pin "2") (pinfunction "2_2") (pintype "passive"))
      (node (ref "IC2") (pin "13") (pinfunction "-IN_13") (pintype "input"))
      (node (ref "R27") (pin "1") (pinfunction "1_1") (pintype "passive"))
      (node (ref "R45") (pin "1") (pinfunction "1_1") (pintype "passive"))
      (node (ref "R46") (pin "2") (pinfunction "2_2") (pintype "passive"))
      (node (ref "R47") (pin "1") (pinfunction "1_1") (pintype "passive"))
      (node (ref "R48") (pin "1") (pinfunction "1_1") (pintype "passive"))
      (node (ref "R49") (pin "2") (pinfunction "2_2") (pintype "passive"))
    )
    (net (code "35") (name "Net-(IC2D-OUT)") (class "Default")
      (node (ref "C22") (pin "1") (pinfunction "1_1") (pintype "passive"))
      (node (ref "IC2") (pin "14") (pinfunction "OUT_14") (pintype "output"))
      (node (ref "R33") (pin "2") (pinfunction "2_2") (pintype "passive"))
      (node (ref "R49") (pin "1") (pinfunction "1_1") (pintype "passive"))
    )
    (net (code "36") (name "Net-(IC3C-IN_N)") (class "Default")
      (node (ref "IC3") (pin "4") (pinfunction "IN_N_4") (pintype "input"))
      (node (ref "R37") (pin "2") (pinfunction "2_2") (pintype "passive"))
      (node (ref "R39") (pin "2") (pinfunction "2_2") (pintype "passive"))
    )
    (net (code "37") (name "Net-(IC3C-I_BIAS)") (class "Default")
      (node (ref "IC3") (pin "1") (pinfunction "I_BIAS_1") (pintype "input"))
      (node (ref "R40") (pin "1") (pinfunction "1_1") (pintype "passive"))
    )
    (net (code "38") (name "Net-(IC3D-IN_N)") (class "Default")
      (node (ref "IC3") (pin "13") (pinfunction "IN_N_13") (pintype "input"))
      (node (ref "R13") (pin "1") (pinfunction "1_1") (pintype "passive"))
      (node (ref "R50") (pin "2") (pinfunction "2_2") (pintype "passive"))
      (node (ref "R54") (pin "2") (pinfunction "2_2") (pintype "passive"))
    )
    (net (code "39") (name "Net-(IC3D-I_BIAS)") (class "Default")
      (node (ref "IC3") (pin "16") (pinfunction "I_BIAS_16") (pintype "input"))
      (node (ref "R51") (pin "1") (pinfunction "1_1") (pintype "passive"))
    )
    (net (code "40") (name "Net-(IC4C-IN_N)") (class "Default")
      (node (ref "IC4") (pin "4") (pinfunction "IN_N_4") (pintype "input"))
      (node (ref "R41") (pin "2") (pinfunction "2_2") (pintype "passive"))
      (node (ref "R42") (pin "2") (pinfunction "2_2") (pintype "passive"))
    )
    (net (code "41") (name "Net-(IC4C-I_BIAS)") (class "Default")
      (node (ref "IC4") (pin "1") (pinfunction "I_BIAS_1") (pintype "input"))
      (node (ref "R43") (pin "1") (pinfunction "1_1") (pintype "passive"))
    )
    (net (code "42") (name "Net-(IC4C-OUT)") (class "Default")
      (node (ref "C1") (pin "1") (pinfunction "1_1") (pintype "passive"))
      (node (ref "IC4") (pin "5") (pinfunction "OUT_5") (pintype "output"))
      (node (ref "Q4") (pin "3") (pinfunction "P$3_3") (pintype "bidirectional"))
    )
    (net (code "43") (name "Net-(IC4D-IN_N)") (class "Default")
      (node (ref "IC4") (pin "13") (pinfunction "IN_N_13") (pintype "input"))
      (node (ref "R52") (pin "2") (pinfunction "2_2") (pintype "passive"))
      (node (ref "R53") (pin "2") (pinfunction "2_2") (pintype "passive"))
    )
    (net (code "44") (name "Net-(IC4D-I_BIAS)") (class "Default")
      (node (ref "IC4") (pin "16") (pinfunction "I_BIAS_16") (pintype "input"))
      (node (ref "R44") (pin "1") (pinfunction "1_1") (pintype "passive"))
    )
    (net (code "45") (name "Net-(IC4D-OUT)") (class "Default")
      (node (ref "C3") (pin "1") (pinfunction "1_1") (pintype "passive"))
      (node (ref "IC4") (pin "12") (pinfunction "OUT_12") (pintype "output"))
      (node (ref "Q3") (pin "3") (pinfunction "P$3_3") (pintype "bidirectional"))
    )
    (net (code "46") (name "Net-(IC5C-IN_N)") (class "Default")
      (node (ref "IC5") (pin "4") (pinfunction "IN_N_4") (pintype "input"))
      (node (ref "R56") (pin "1") (pinfunction "1_1") (pintype "passive"))
      (node (ref "R57") (pin "2") (pinfunction "2_2") (pintype "passive"))
    )
    (net (code "47") (name "Net-(IC5C-I_BIAS)") (class "Default")
      (node (ref "IC5") (pin "1") (pinfunction "I_BIAS_1") (pintype "input"))
      (node (ref "R58") (pin "1") (pinfunction "1_1") (pintype "passive"))
    )
    (net (code "48") (name "Net-(IC5C-OUT)") (class "Default")
      (node (ref "C2") (pin "1") (pinfunction "1_1") (pintype "passive"))
      (node (ref "IC5") (pin "5") (pinfunction "OUT_5") (pintype "output"))
      (node (ref "Q5") (pin "3") (pinfunction "P$3_3") (pintype "bidirectional"))
    )
    (net (code "49") (name "Net-(IC5D-IN_N)") (class "Default")
      (node (ref "IC5") (pin "13") (pinfunction "IN_N_13") (pintype "input"))
      (node (ref "R64") (pin "2") (pinfunction "2_2") (pintype "passive"))
      (node (ref "R65") (pin "2") (pinfunction "2_2") (pintype "passive"))
    )
    (net (code "50") (name "Net-(IC5D-I_BIAS)") (class "Default")
      (node (ref "IC5") (pin "16") (pinfunction "I_BIAS_16") (pintype "input"))
      (node (ref "R66") (pin "1") (pinfunction "1_1") (pintype "passive"))
    )
    (net (code "51") (name "Net-(IC5D-OUT)") (class "Default")
      (node (ref "C6") (pin "1") (pinfunction "1_1") (pintype "passive"))
      (node (ref "IC5") (pin "12") (pinfunction "OUT_12") (pintype "output"))
      (node (ref "Q6") (pin "3") (pinfunction "P$3_3") (pintype "bidirectional"))
    )
    (net (code "52") (name "Net-(IC7A-I)") (class "Default")
      (node (ref "IC7") (pin "1") (pinfunction "I_1") (pintype "input"))
      (node (ref "R77") (pin "1") (pinfunction "1_1") (pintype "passive"))
    )
    (net (code "53") (name "Net-(IC7A-O)") (class "Default")
      (node (ref "IC7") (pin "2") (pinfunction "O_2") (pintype "output"))
      (node (ref "U3") (pin "12") (pinfunction "RESET1_12") (pintype "passive"))
      (node (ref "U3") (pin "4") (pinfunction "RESET2_4") (pintype "passive"))
    )
    (net (code "54") (name "Net-(IC7B-I)") (class "Default")
      (node (ref "C28") (pin "1") (pinfunction "1_1") (pintype "passive"))
      (node (ref "IC7") (pin "3") (pinfunction "I_3") (pintype "input"))
      (node (ref "R75") (pin "2") (pinfunction "2_2") (pintype "passive"))
      (node (ref "R76") (pin "2") (pinfunction "2_2") (pintype "passive"))
    )
    (net (code "55") (name "Net-(IC7B-O)") (class "Default")
      (node (ref "IC7") (pin "4") (pinfunction "O_4") (pintype "output"))
      (node (ref "U3") (pin "3") (pinfunction "CLOCK2_3") (pintype "passive"))
    )
    (net (code "56") (name "Net-(IN1-3)") (class "Default")
      (node (ref "IN1") (pin "P3") (pinfunction "3_P3") (pintype "passive"))
      (node (ref "R1") (pin "1") (pinfunction "1_1") (pintype "passive"))
    )
    (net (code "57") (name "Net-(IN2-3)") (class "Default")
      (node (ref "IN2") (pin "P3") (pinfunction "3_P3") (pintype "passive"))
      (node (ref "LEVEL_2") (pin "P$1") (pinfunction "E_P$1") (pintype "passive"))
    )
    (net (code "58") (name "Net-(LEVEL_2-S)") (class "Default")
      (node (ref "LEVEL_2") (pin "P$2") (pinfunction "S_P$2") (pintype "passive"))
      (node (ref "R3") (pin "1") (pinfunction "1_1") (pintype "passive"))
    )
    (net (code "59") (name "Net-(P1-Pad2)") (class "Default")
      (node (ref "P1") (pin "2") (pinfunction "2_2") (pintype "bidirectional"))
      (node (ref "POWER!") (pin "10") (pinfunction "+12V_10") (pintype "bidirectional"))
      (node (ref "POWER!") (pin "9") (pinfunction "+12V_9") (pintype "bidirectional"))
    )
    (net (code "60") (name "Net-(P2-Pad2)") (class "Default")
      (node (ref "P2") (pin "2") (pinfunction "2_2") (pintype "bidirectional"))
      (node (ref "POWER!") (pin "1") (pinfunction "-12V_1") (pintype "bidirectional"))
      (node (ref "POWER!") (pin "2") (pinfunction "-12V_2") (pintype "bidirectional"))
    )
    (net (code "61") (name "Net-(Q1-E)") (class "Default")
      (node (ref "Q1") (pin "1") (pinfunction "E_1") (pintype "bidirectional"))
      (node (ref "Q1") (pin "4") (pinfunction "H_4") (pintype "bidirectional"))
      (node (ref "R12") (pin "1") (pinfunction "1_1") (pintype "passive"))
    )
    (net (code "62") (name "Net-(Q1-I)") (class "Default")
      (node (ref "Q1") (pin "5") (pinfunction "I_5") (pintype "bidirectional"))
      (node (ref "R20") (pin "1") (pinfunction "1_1") (pintype "passive"))
      (node (ref "R21") (pin "1") (pinfunction "1_1") (pintype "passive"))
      (node (ref "R24") (pin "1") (pinfunction "1_1") (pintype "passive"))
    )
    (net (code "63") (name "Net-(Q1-J)") (class "Default")
      (node (ref "C16") (pin "2") (pinfunction "2_2") (pintype "passive"))
      (node (ref "Q1") (pin "6") (pinfunction "J_6") (pintype "bidirectional"))
      (node (ref "R10") (pin "1") (pinfunction "1_1") (pintype "passive"))
      (node (ref "U1") (pin "4") (pinfunction "-IN_4") (pintype "input"))
    )
    (net (code "64") (name "Net-(Q2-E)") (class "Default")
      (node (ref "Q2") (pin "1") (pinfunction "E_1") (pintype "bidirectional"))
      (node (ref "Q2") (pin "4") (pinfunction "H_4") (pintype "bidirectional"))
      (node (ref "R31") (pin "2") (pinfunction "2_2") (pintype "passive"))
    )
    (net (code "65") (name "Net-(Q2-I)") (class "Default")
      (node (ref "Q2") (pin "5") (pinfunction "I_5") (pintype "bidirectional"))
      (node (ref "R23") (pin "2") (pinfunction "2_2") (pintype "passive"))
      (node (ref "R28") (pin "2") (pinfunction "2_2") (pintype "passive"))
      (node (ref "R29") (pin "2") (pinfunction "2_2") (pintype "passive"))
      (node (ref "R30") (pin "2") (pinfunction "2_2") (pintype "passive"))
    )
    (net (code "66") (name "Net-(Q2-J)") (class "Default")
      (node (ref "C17") (pin "2") (pinfunction "2_2") (pintype "passive"))
      (node (ref "Q2") (pin "6") (pinfunction "J_6") (pintype "bidirectional"))
      (node (ref "R16") (pin "2") (pinfunction "2_2") (pintype "passive"))
      (node (ref "U2") (pin "4") (pinfunction "-IN_4") (pintype "input"))
    )
    (net (code "67") (name "Net-(Q3-P$1)") (class "Default")
      (node (ref "C15") (pin "1") (pinfunction "1_1") (pintype "passive"))
      (node (ref "Q3") (pin "1") (pinfunction "P$1_1") (pintype "bidirectional"))
      (node (ref "R14") (pin "2") (pinfunction "2_2") (pintype "passive"))
      (node (ref "R15") (pin "2") (pinfunction "2_2") (pintype "passive"))
      (node (ref "R25") (pin "1") (pinfunction "1_1") (pintype "passive"))
      (node (ref "R26") (pin "1") (pinfunction "1_1") (pintype "passive"))
    )
    (net (code "68") (name "Net-(Q4-P$1)") (class "Default")
      (node (ref "Q4") (pin "1") (pinfunction "P$1_1") (pintype "bidirectional"))
      (node (ref "R52") (pin "1") (pinfunction "1_1") (pintype "passive"))
      (node (ref "R54") (pin "1") (pinfunction "1_1") (pintype "passive"))
      (node (ref "R55") (pin "2") (pinfunction "2_2") (pintype "passive"))
    )
    (net (code "69") (name "Net-(Q5-P$1)") (class "Default")
      (node (ref "C26") (pin "1") (pinfunction "1_1") (pintype "passive"))
      (node (ref "Q5") (pin "1") (pinfunction "P$1_1") (pintype "bidirectional"))
      (node (ref "R59") (pin "1") (pinfunction "1_1") (pintype "passive"))
      (node (ref "R60") (pin "2") (pinfunction "2_2") (pintype "passive"))
      (node (ref "R61") (pin "2") (pinfunction "2_2") (pintype "passive"))
    )
    (net (code "70") (name "Net-(Q6-P$1)") (class "Default")
      (node (ref "Q6") (pin "1") (pinfunction "P$1_1") (pintype "bidirectional"))
      (node (ref "R38") (pin "2") (pinfunction "2_2") (pintype "passive"))
      (node (ref "R39") (pin "1") (pinfunction "1_1") (pintype "passive"))
      (node (ref "R56") (pin "2") (pinfunction "2_2") (pintype "passive"))
      (node (ref "R68") (pin "1") (pinfunction "1_1") (pintype "passive"))
    )
    (net (code "71") (name "Net-(R20-Pad2)") (class "Default")
      (node (ref "R20") (pin "2") (pinfunction "2_2") (pintype "passive"))
      (node (ref "R22") (pin "2") (pinfunction "2_2") (pintype "passive"))
      (node (ref "R33") (pin "1") (pinfunction "1_1") (pintype "passive"))
    )
    (net (code "72") (name "Net-(R21-Pad2)") (class "Default")
      (node (ref "R21") (pin "2") (pinfunction "2_2") (pintype "passive"))
      (node (ref "R22") (pin "1") (pinfunction "1_1") (pintype "passive"))
    )
    (net (code "73") (name "Net-(RES-E)") (class "Default")
      (node (ref "R73") (pin "2") (pinfunction "2_2") (pintype "passive"))
      (node (ref "RES") (pin "P$1") (pinfunction "E_P$1") (pintype "passive"))
    )
    (net (code "74") (name "Net-(RES-S)") (class "Default")
      (node (ref "R36") (pin "2") (pinfunction "2_2") (pintype "passive"))
      (node (ref "RES") (pin "P$2") (pinfunction "S_P$2") (pintype "passive"))
    )
    (net (code "75") (name "Net-(RES_CV-3)") (class "Default")
      (node (ref "R19") (pin "1") (pinfunction "1_1") (pintype "passive"))
      (node (ref "RES_CV") (pin "P3") (pinfunction "3_P3") (pintype "passive"))
    )
    (net (code "76") (name "Net-(SW1-S)") (class "Default")
      (node (ref "R76") (pin "1") (pinfunction "1_1") (pintype "passive"))
      (node (ref "SW1") (pin "A1") (pinfunction "S_A1") (pintype "passive"))
      (node (ref "SW1") (pin "A2") (pinfunction "S1_A2") (pintype "passive"))
    )
    (net (code "77") (name "Net-(TR1-P$2)") (class "Default")
      (node (ref "R47") (pin "2") (pinfunction "2_2") (pintype "passive"))
      (node (ref "TR1") (pin "2") (pinfunction "P$2_2") (pintype "bidirectional"))
    )
    (net (code "78") (name "Net-(TR2-P$2)") (class "Default")
      (node (ref "R30") (pin "1") (pinfunction "1_1") (pintype "passive"))
      (node (ref "TR2") (pin "2") (pinfunction "P$2_2") (pintype "bidirectional"))
    )
    (net (code "79") (name "Net-(U1-OUT)") (class "Default")
      (node (ref "C16") (pin "1") (pinfunction "1_1") (pintype "passive"))
      (node (ref "R12") (pin "2") (pinfunction "2_2") (pintype "passive"))
      (node (ref "U1") (pin "1") (pinfunction "OUT_1") (pintype "output"))
    )
    (net (code "80") (name "Net-(U2-OUT)") (class "Default")
      (node (ref "C17") (pin "1") (pinfunction "1_1") (pintype "passive"))
      (node (ref "R31") (pin "1") (pinfunction "1_1") (pintype "passive"))
      (node (ref "U2") (pin "1") (pinfunction "OUT_1") (pintype "output"))
    )
    (net (code "81") (name "Net-(U3-CLOCK1)") (class "Default")
      (node (ref "U3") (pin "13") (pinfunction "CLOCK1_13") (pintype "passive"))
      (node (ref "U3") (pin "2") (pinfunction "~{Q2}_2") (pintype "output"))
    )
    (net (code "82") (name "Net-(U4-COMMON)") (class "Default")
      (node (ref "R71") (pin "2") (pinfunction "2_2") (pintype "passive"))
      (node (ref "U4") (pin "13") (pinfunction "COMMON_13") (pintype "bidirectional"))
    )
    (net (code "83") (name "Net-(U4-COMMON_2)") (class "Default")
      (node (ref "R72") (pin "2") (pinfunction "2_2") (pintype "passive"))
      (node (ref "U4") (pin "3") (pinfunction "COMMON_2_3") (pintype "bidirectional"))
    )
    (net (code "84") (name "OUT2A") (class "Default")
      (node (ref "IC6") (pin "4") (pinfunction "S1A_4") (pintype "passive"))
      (node (ref "IC6") (pin "5") (pinfunction "S2A_5") (pintype "passive"))
      (node (ref "R26") (pin "2") (pinfunction "2_2") (pintype "passive"))
    )
    (net (code "85") (name "OUT2B") (class "Default")
      (node (ref "IC6") (pin "12") (pinfunction "S2B_12") (pintype "passive"))
      (node (ref "R25") (pin "2") (pinfunction "2_2") (pintype "passive"))
    )
    (net (code "86") (name "OUT4") (class "Default")
      (node (ref "IC6") (pin "11") (pinfunction "S3B_11") (pintype "passive"))
      (node (ref "IC6") (pin "13") (pinfunction "S1B_13") (pintype "passive"))
      (node (ref "R59") (pin "2") (pinfunction "2_2") (pintype "passive"))
    )
    (net (code "87") (name "OUTPUT") (class "Default")
      (node (ref "OUT") (pin "P3") (pinfunction "3_P3") (pintype "passive"))
      (node (ref "R2") (pin "2") (pinfunction "2_2") (pintype "passive"))
    )
    (net (code "88") (name "RES_CTRL") (class "Default")
      (node (ref "Q2") (pin "3") (pinfunction "G_3") (pintype "bidirectional"))
      (node (ref "R40") (pin "2") (pinfunction "2_2") (pintype "passive"))
      (node (ref "R51") (pin "2") (pinfunction "2_2") (pintype "passive"))
    )
    (net (code "89") (name "SUM1") (class "Default")
      (node (ref "IC6") (pin "6") (pinfunction "S3A_6") (pintype "passive"))
      (node (ref "IC6") (pin "7") (pinfunction "S4A_7") (pintype "passive"))
      (node (ref "R35") (pin "2") (pinfunction "2_2") (pintype "passive"))
    )
    (net (code "90") (name "SUM2") (class "Default")
      (node (ref "IC6") (pin "10") (pinfunction "S4B_10") (pintype "passive"))
      (node (ref "R62") (pin "2") (pinfunction "2_2") (pintype "passive"))
    )
    (net (code "91") (name "SWX1") (class "Default")
      (node (ref "IC6") (pin "8") (pinfunction "DA_8") (pintype "passive"))
      (node (ref "R69") (pin "1") (pinfunction "1_1") (pintype "passive"))
    )
    (net (code "92") (name "SWY2") (class "Default")
      (node (ref "C5") (pin "-") (pinfunction "-_-") (pintype "passive"))
      (node (ref "IC6") (pin "9") (pinfunction "DB_9") (pintype "passive"))
    )
    (net (code "93") (name "unconnected-(CV1-2-PadP2)") (class "Default")
      (node (ref "CV1") (pin "P2") (pinfunction "2_P2") (pintype "passive"))
    )
    (net (code "94") (name "unconnected-(CV2-2-PadP2)") (class "Default")
      (node (ref "CV2") (pin "P2") (pinfunction "2_P2") (pintype "passive"))
    )
    (net (code "95") (name "unconnected-(IC3A-B-Pad7)") (class "Default")
      (node (ref "IC3") (pin "7") (pinfunction "B_7") (pintype "passive"))
    )
    (net (code "96") (name "unconnected-(IC3A-E-Pad8)") (class "Default")
      (node (ref "IC3") (pin "8") (pinfunction "E_8") (pintype "passive"))
    )
    (net (code "97") (name "unconnected-(IC3B-B-Pad10)") (class "Default")
      (node (ref "IC3") (pin "10") (pinfunction "B_10") (pintype "passive"))
    )
    (net (code "98") (name "unconnected-(IC3B-E-Pad9)") (class "Default")
      (node (ref "IC3") (pin "9") (pinfunction "E_9") (pintype "passive"))
    )
    (net (code "99") (name "unconnected-(IC3C-I_DIODE-Pad2)") (class "Default")
      (node (ref "IC3") (pin "2") (pinfunction "I_DIODE_2") (pintype "input"))
    )
    (net (code "100") (name "unconnected-(IC3D-I_DIODE-Pad15)") (class "Default")
      (node (ref "IC3") (pin "15") (pinfunction "I_DIODE_15") (pintype "input"))
    )
    (net (code "101") (name "unconnected-(IC4A-B-Pad7)") (class "Default")
      (node (ref "IC4") (pin "7") (pinfunction "B_7") (pintype "passive"))
    )
    (net (code "102") (name "unconnected-(IC4A-E-Pad8)") (class "Default")
      (node (ref "IC4") (pin "8") (pinfunction "E_8") (pintype "passive"))
    )
    (net (code "103") (name "unconnected-(IC4B-B-Pad10)") (class "Default")
      (node (ref "IC4") (pin "10") (pinfunction "B_10") (pintype "passive"))
    )
    (net (code "104") (name "unconnected-(IC4B-E-Pad9)") (class "Default")
      (node (ref "IC4") (pin "9") (pinfunction "E_9") (pintype "passive"))
    )
    (net (code "105") (name "unconnected-(IC4C-I_DIODE-Pad2)") (class "Default")
      (node (ref "IC4") (pin "2") (pinfunction "I_DIODE_2") (pintype "input"))
    )
    (net (code "106") (name "unconnected-(IC4D-I_DIODE-Pad15)") (class "Default")
      (node (ref "IC4") (pin "15") (pinfunction "I_DIODE_15") (pintype "input"))
    )
    (net (code "107") (name "unconnected-(IC5A-B-Pad7)") (class "Default")
      (node (ref "IC5") (pin "7") (pinfunction "B_7") (pintype "passive"))
    )
    (net (code "108") (name "unconnected-(IC5A-E-Pad8)") (class "Default")
      (node (ref "IC5") (pin "8") (pinfunction "E_8") (pintype "passive"))
    )
    (net (code "109") (name "unconnected-(IC5B-B-Pad10)") (class "Default")
      (node (ref "IC5") (pin "10") (pinfunction "B_10") (pintype "passive"))
    )
    (net (code "110") (name "unconnected-(IC5B-E-Pad9)") (class "Default")
      (node (ref "IC5") (pin "9") (pinfunction "E_9") (pintype "passive"))
    )
    (net (code "111") (name "unconnected-(IC5C-I_DIODE-Pad2)") (class "Default")
      (node (ref "IC5") (pin "2") (pinfunction "I_DIODE_2") (pintype "input"))
    )
    (net (code "112") (name "unconnected-(IC5D-I_DIODE-Pad15)") (class "Default")
      (node (ref "IC5") (pin "15") (pinfunction "I_DIODE_15") (pintype "input"))
    )
    (net (code "113") (name "unconnected-(IC7C-O-Pad6)") (class "Default")
      (node (ref "IC7") (pin "6") (pinfunction "O_6") (pintype "output"))
    )
    (net (code "114") (name "unconnected-(IC7D-O-Pad8)") (class "Default")
      (node (ref "IC7") (pin "8") (pinfunction "O_8") (pintype "output"))
    )
    (net (code "115") (name "unconnected-(IC7E-O-Pad10)") (class "Default")
      (node (ref "IC7") (pin "10") (pinfunction "O_10") (pintype "output"))
    )
    (net (code "116") (name "unconnected-(IC7F-O-Pad12)") (class "Default")
      (node (ref "IC7") (pin "12") (pinfunction "O_12") (pintype "output"))
    )
    (net (code "117") (name "unconnected-(IN1-2-PadP2)") (class "Default")
      (node (ref "IN1") (pin "P2") (pinfunction "2_P2") (pintype "passive"))
    )
    (net (code "118") (name "unconnected-(OUT-2-PadP2)") (class "Default")
      (node (ref "OUT") (pin "P2") (pinfunction "2_P2") (pintype "passive"))
    )
    (net (code "119") (name "unconnected-(RES_CV-2-PadP2)") (class "Default")
      (node (ref "RES_CV") (pin "P2") (pinfunction "2_P2") (pintype "passive"))
    )
    (net (code "120") (name "unconnected-(U3-~{Q1}-Pad14)") (class "Default")
      (node (ref "U3") (pin "14") (pinfunction "~{Q1}_14") (pintype "output"))
    )
    (net (code "121") (name "unconnected-(U4-0_2-Pad12)") (class "Default")
      (node (ref "U4") (pin "12") (pinfunction "0_2_12") (pintype "bidirectional"))
    )
    (net (code "122") (name "unconnected-(U4-2_2-Pad15)") (class "Default")
      (node (ref "U4") (pin "15") (pinfunction "2_2_15") (pintype "bidirectional"))
    )
    (net (code "123") (name "unconnected-(U4-3-Pad4)") (class "Default")
      (node (ref "U4") (pin "4") (pinfunction "3_4") (pintype "bidirectional"))
    )
  )
)
